# IO4-IR-Detector-GBunza-Fingers.net
KiCad netlist of a schematic drawn in EAGLE
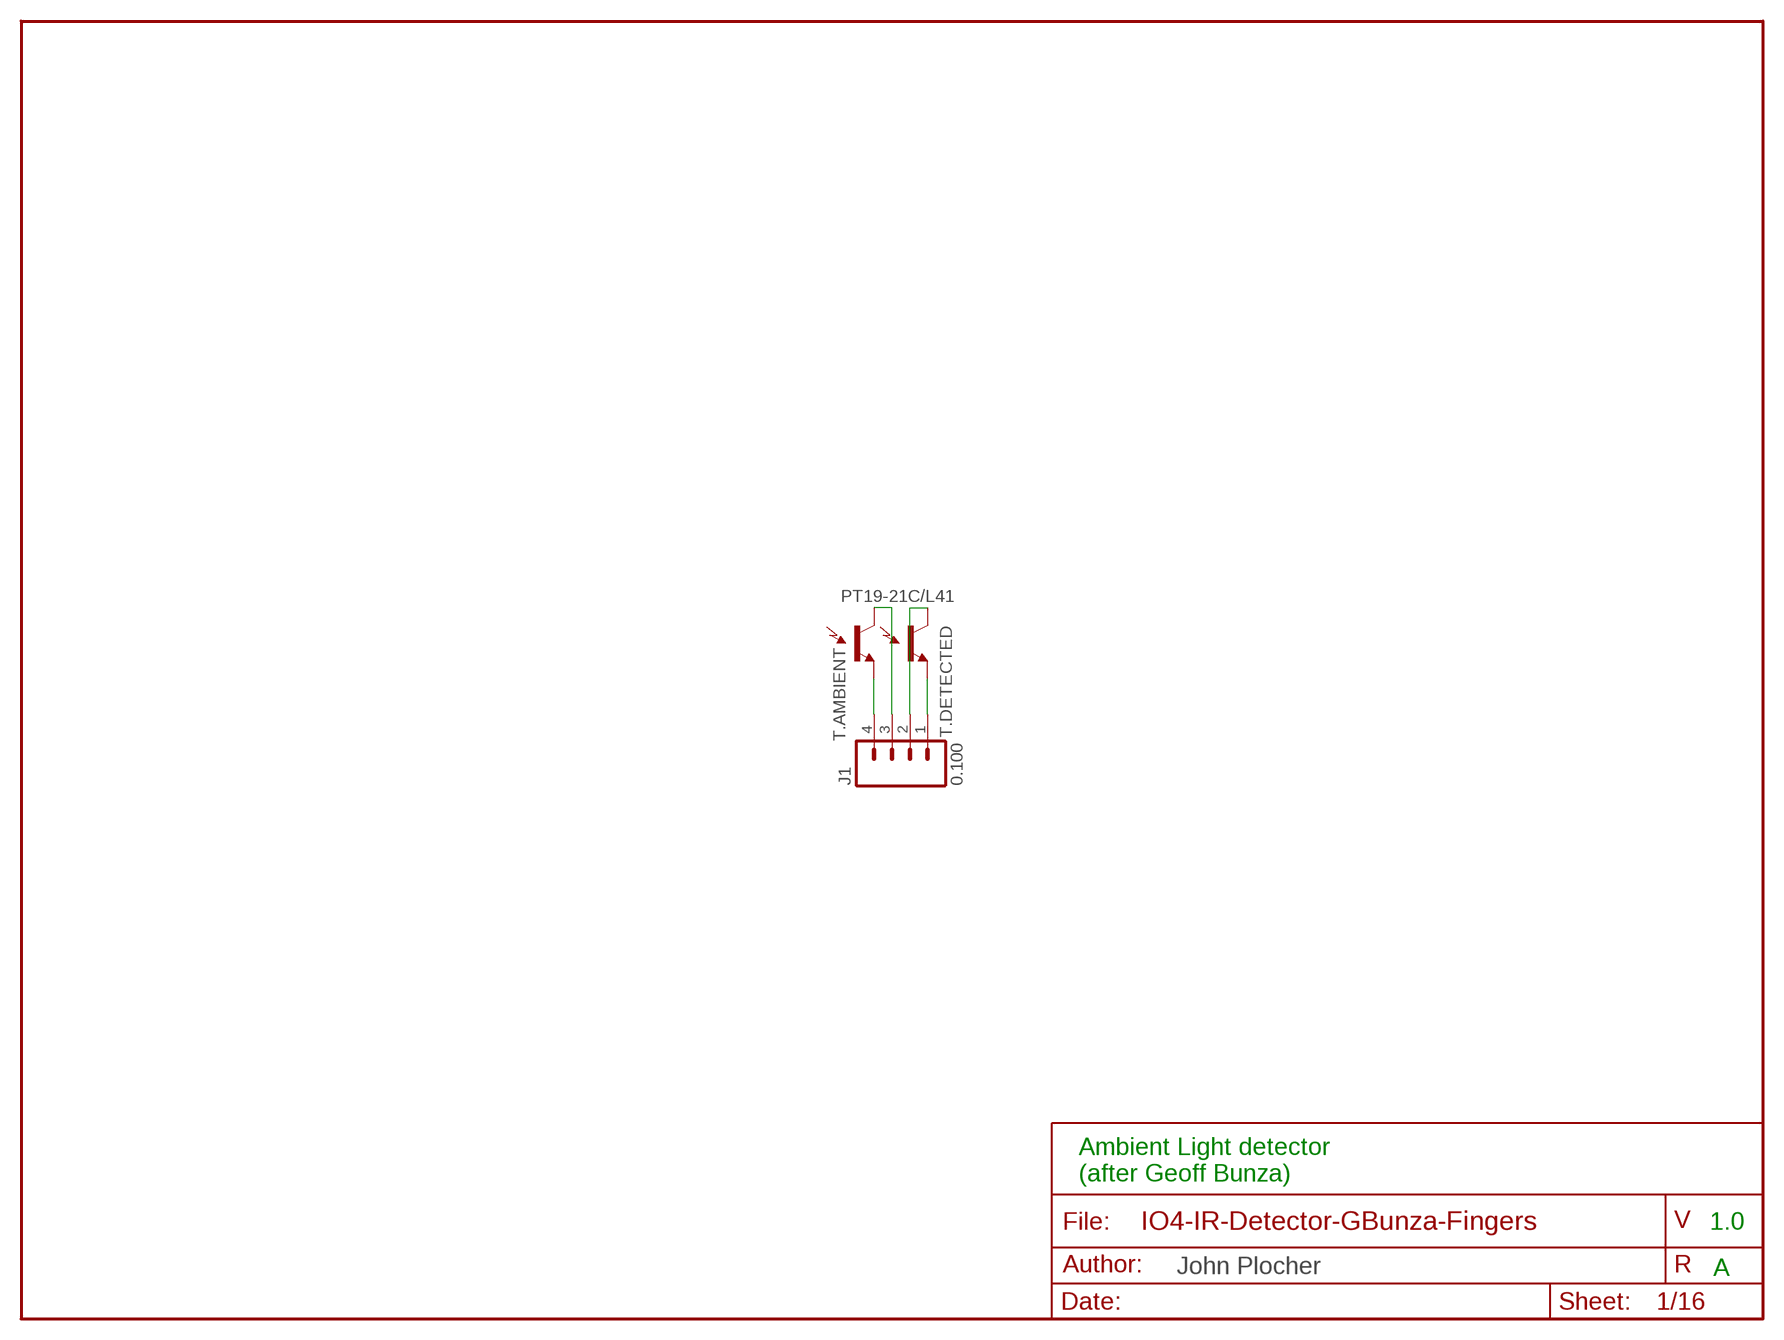
[diagram p0: schematic, sheet 1]
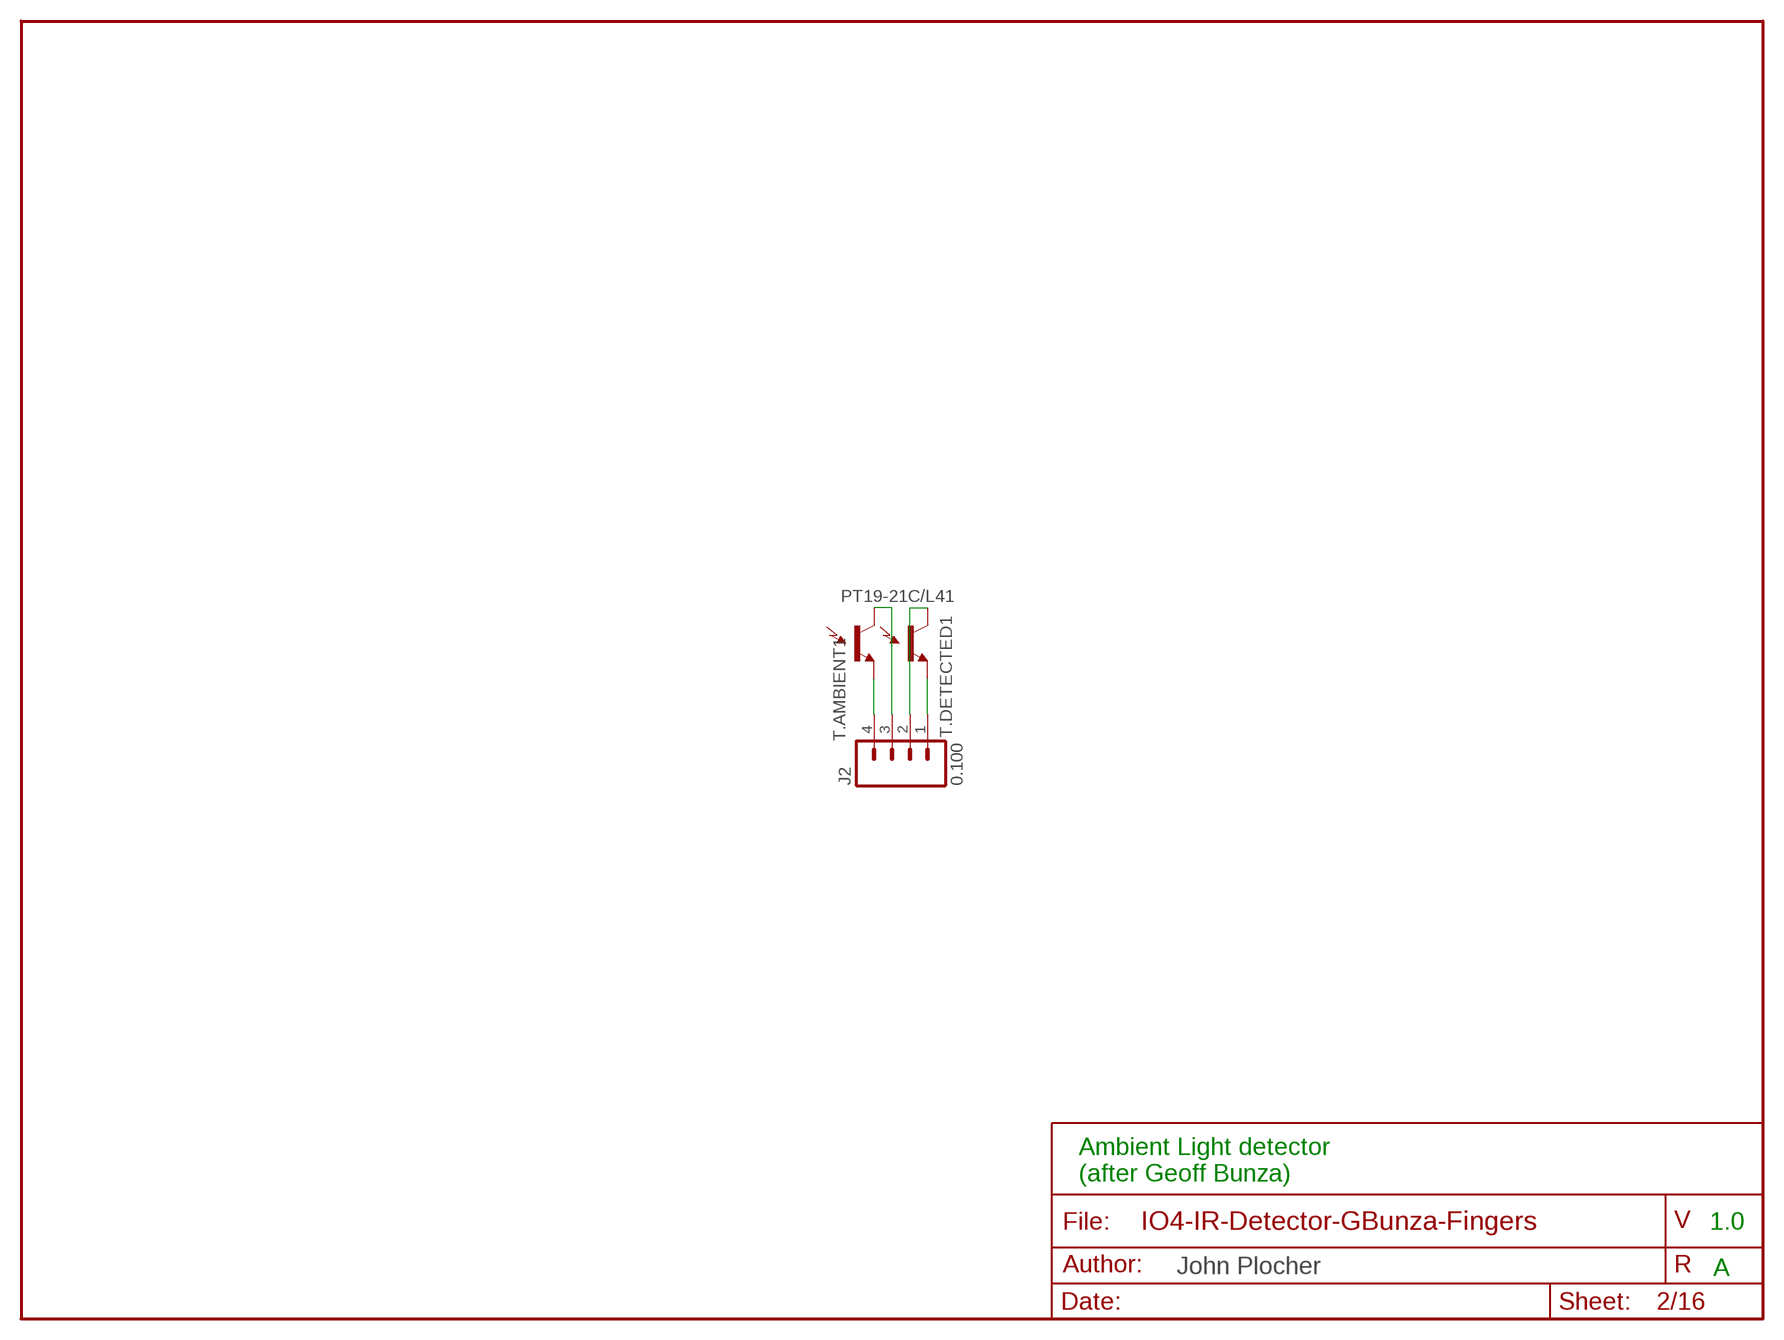
[diagram p1: schematic, sheet 2]
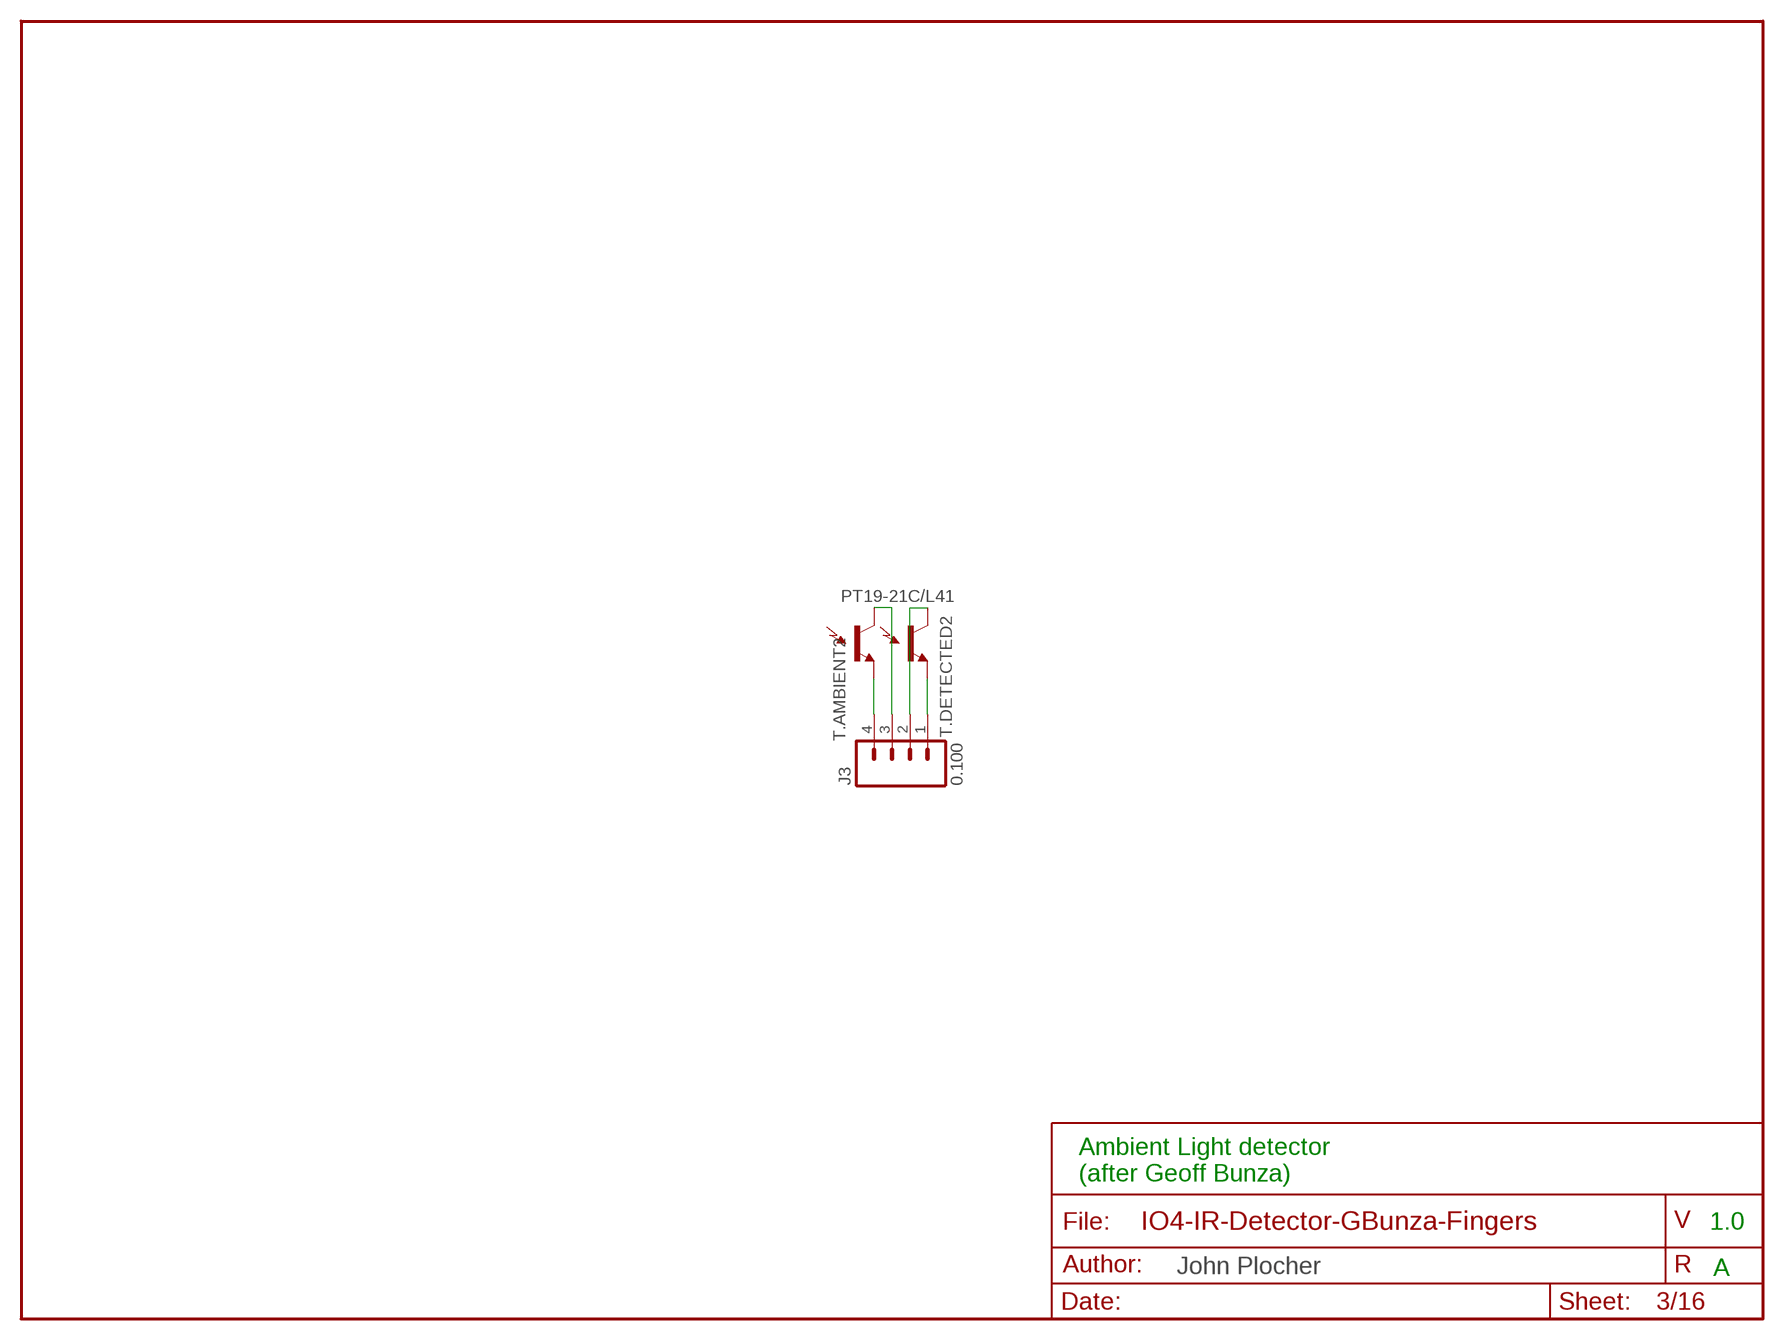
[diagram p2: schematic, sheet 3]
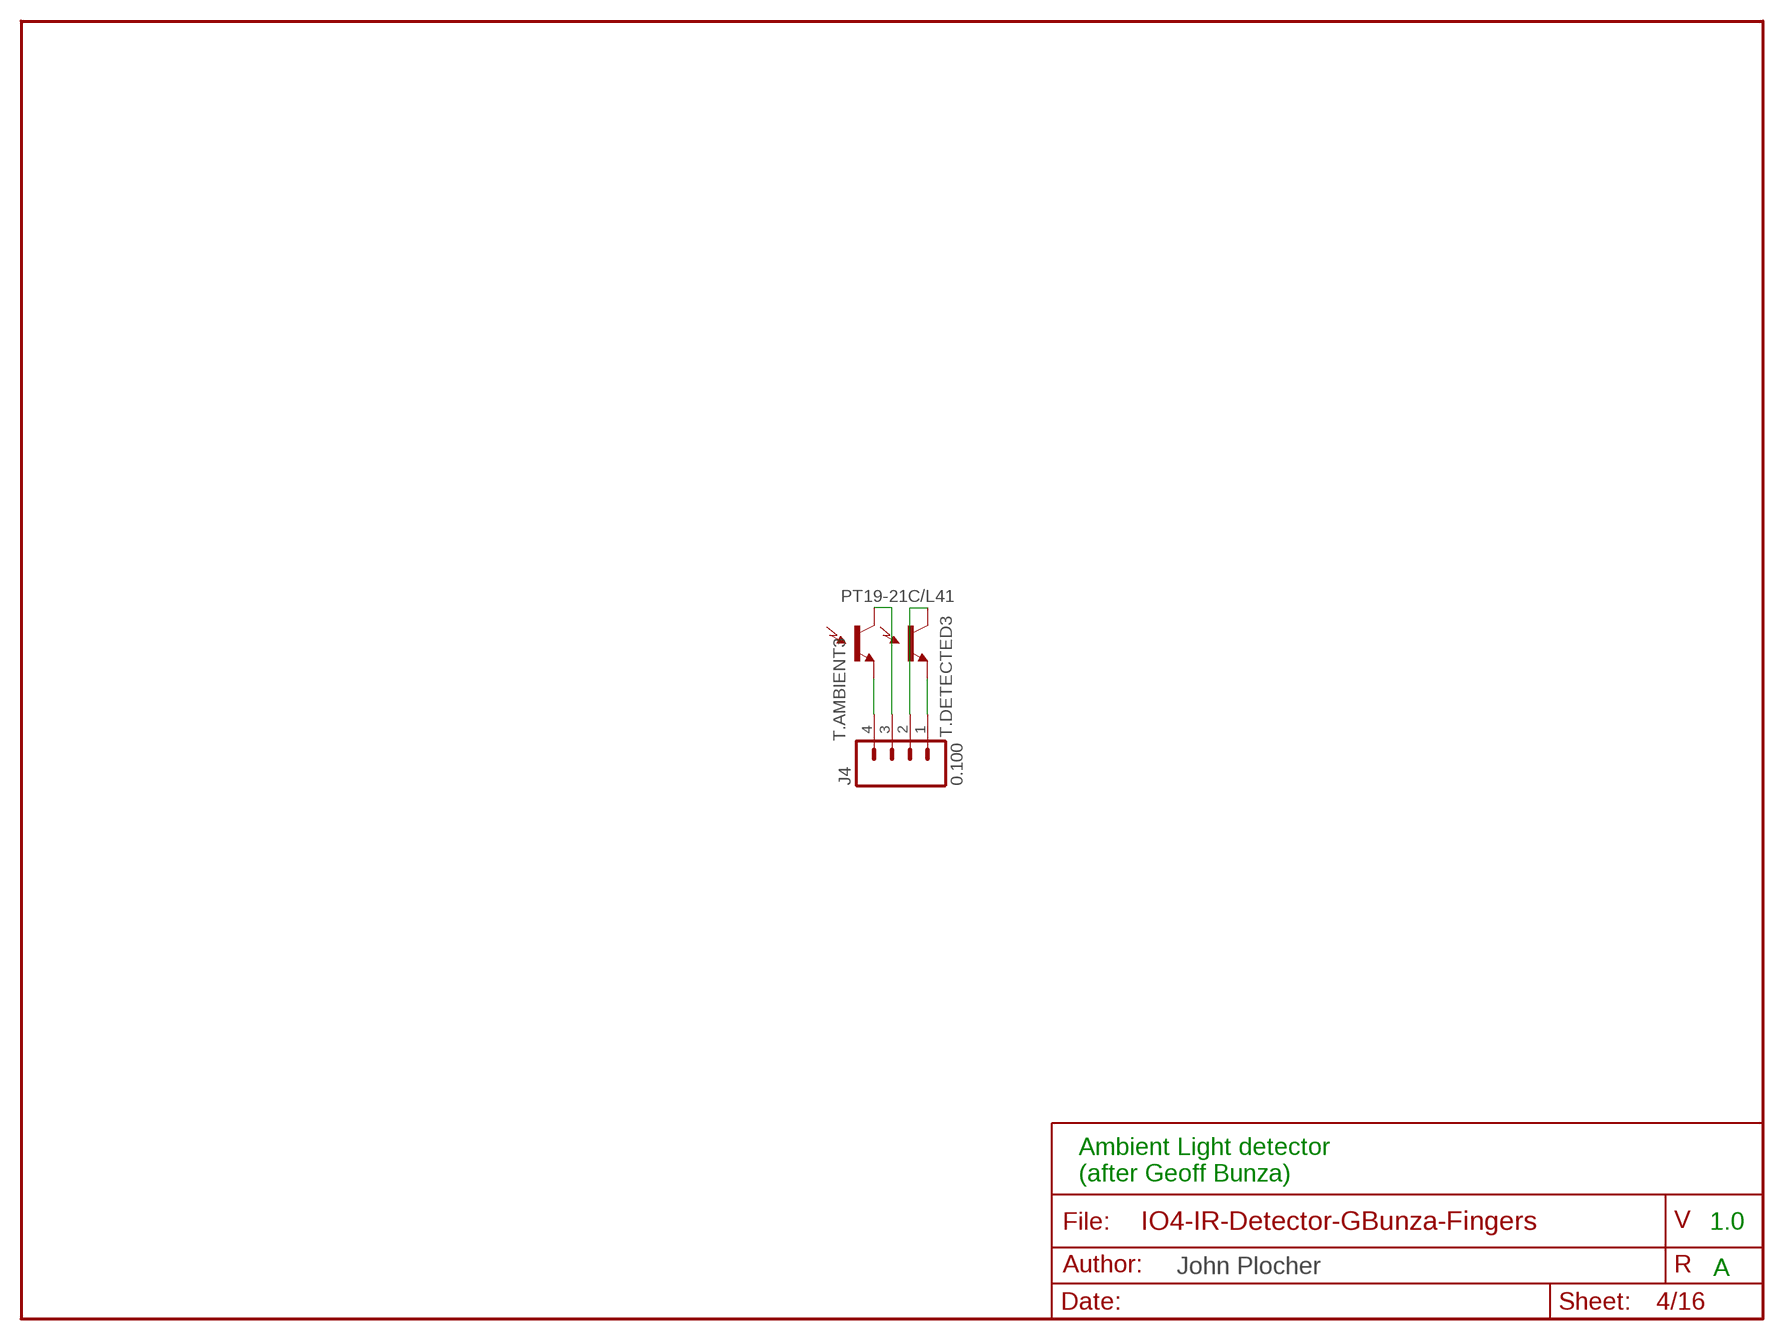
[diagram p3: schematic, sheet 4]
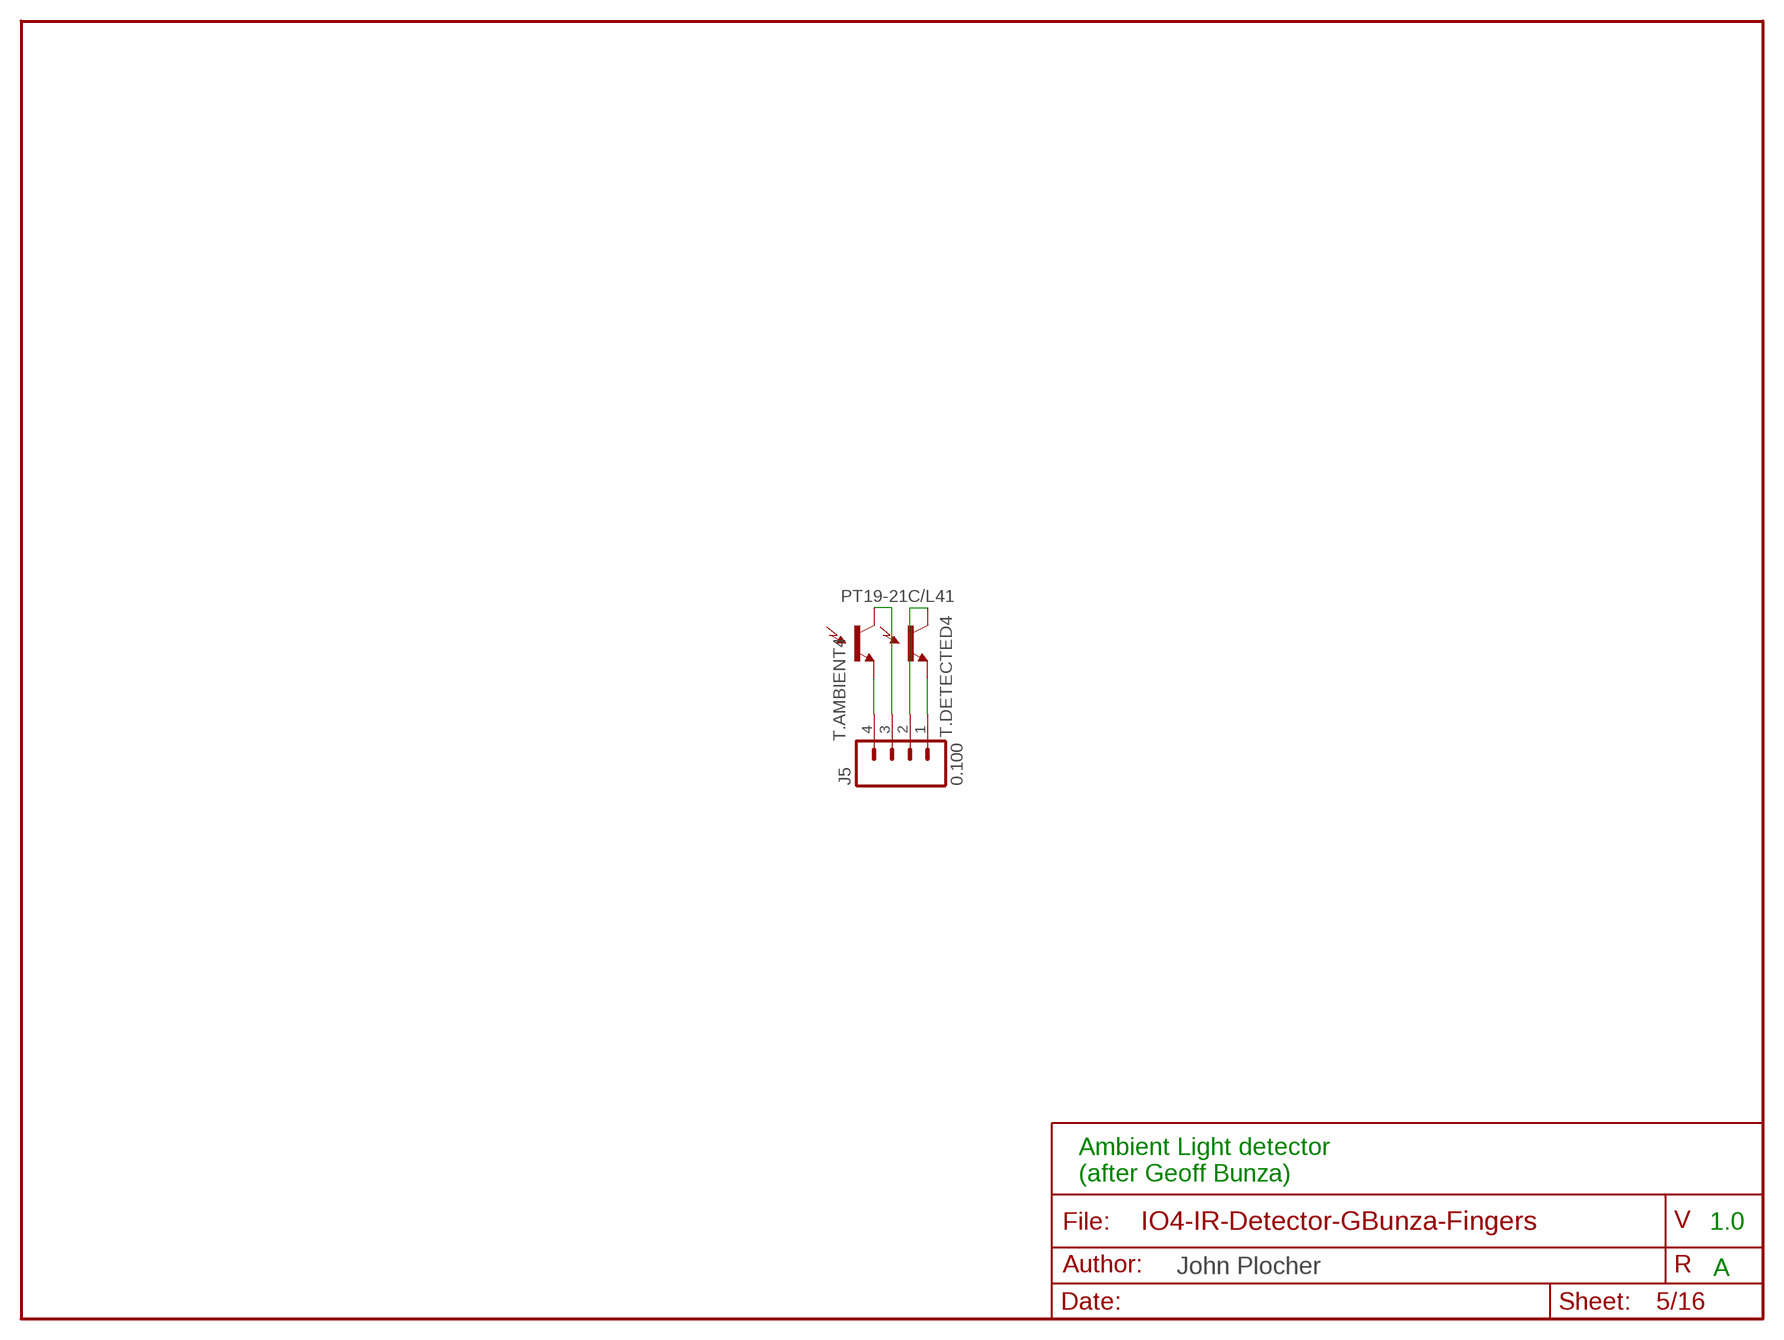
[diagram p4: schematic, sheet 5]
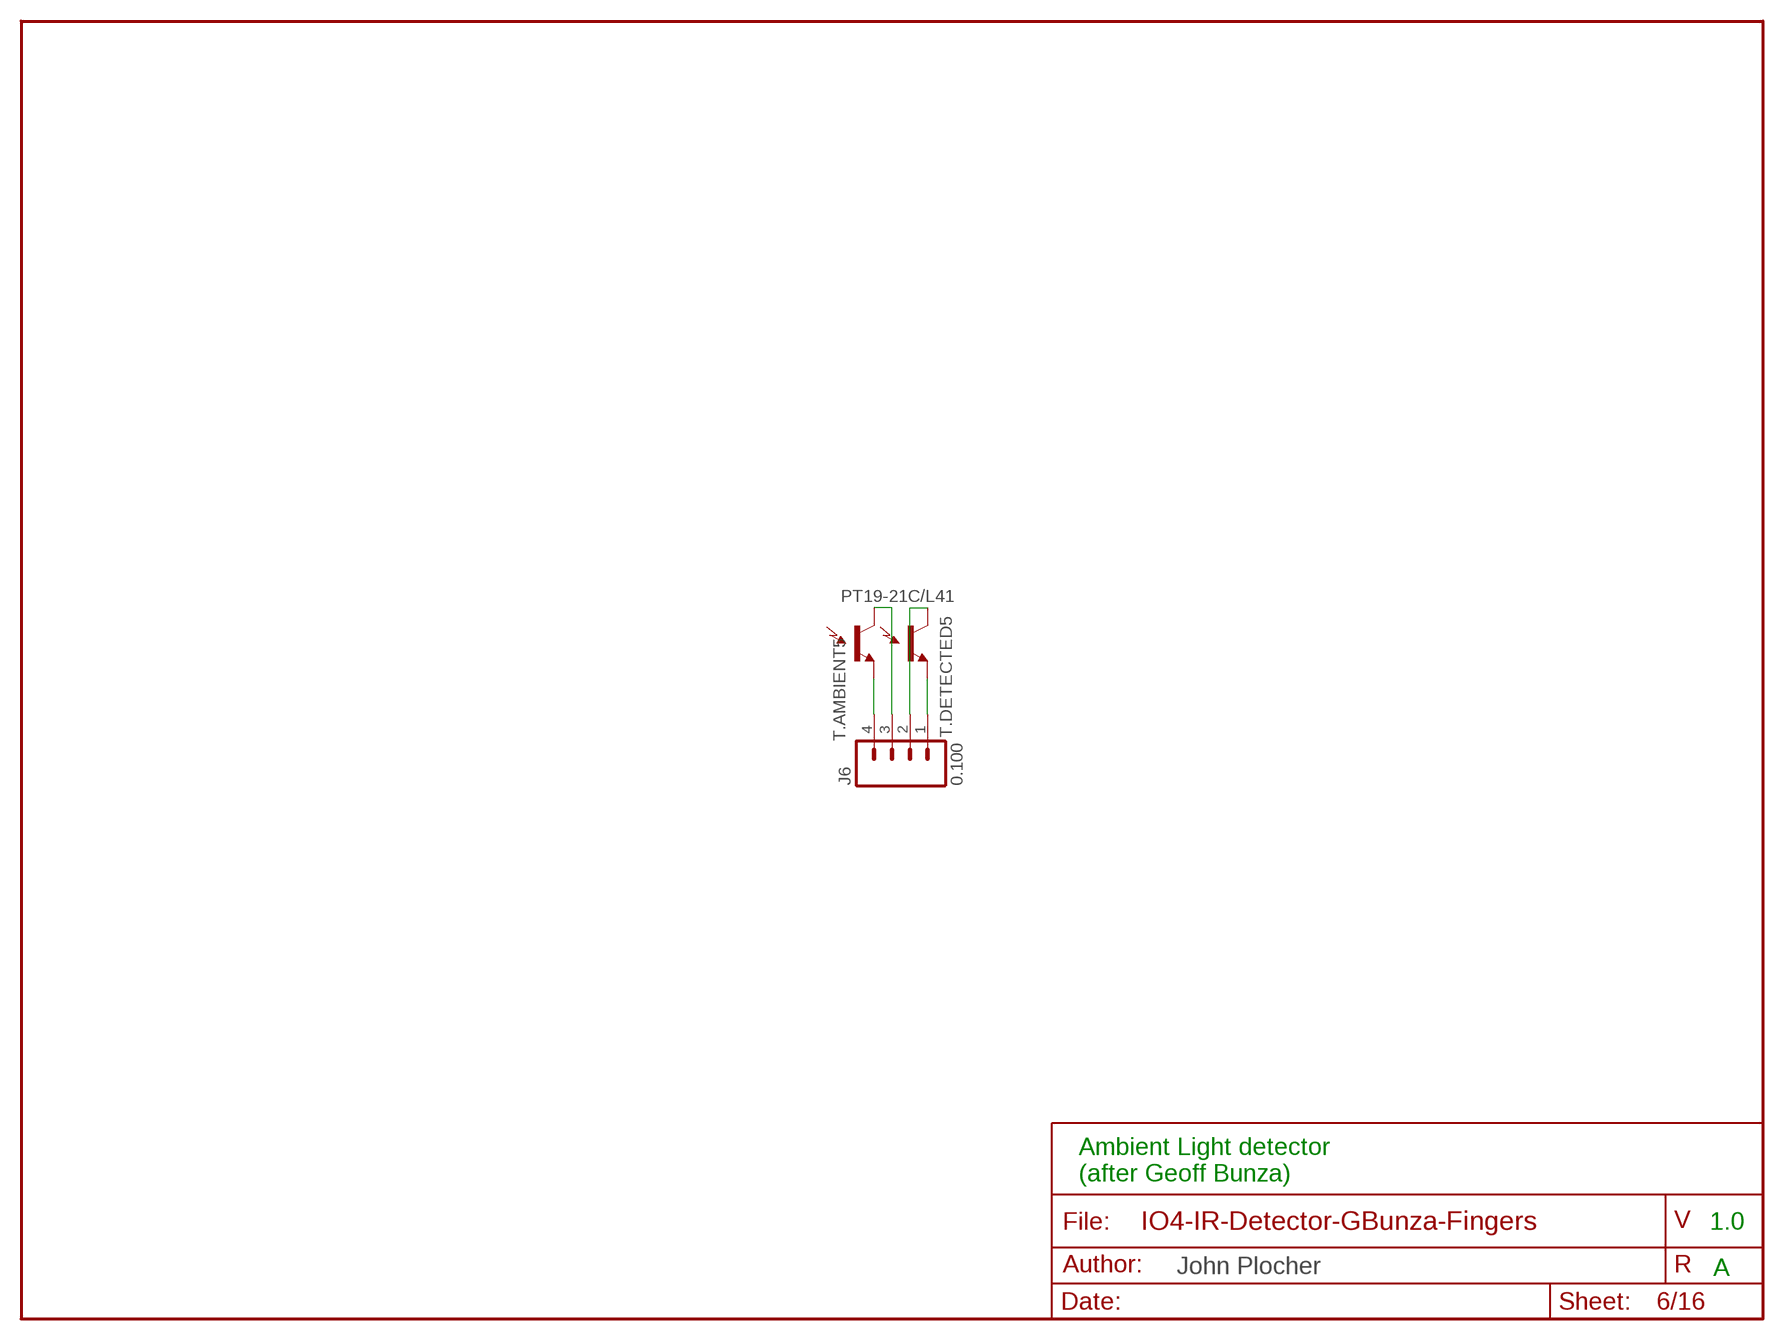
[diagram p5: schematic, sheet 6]
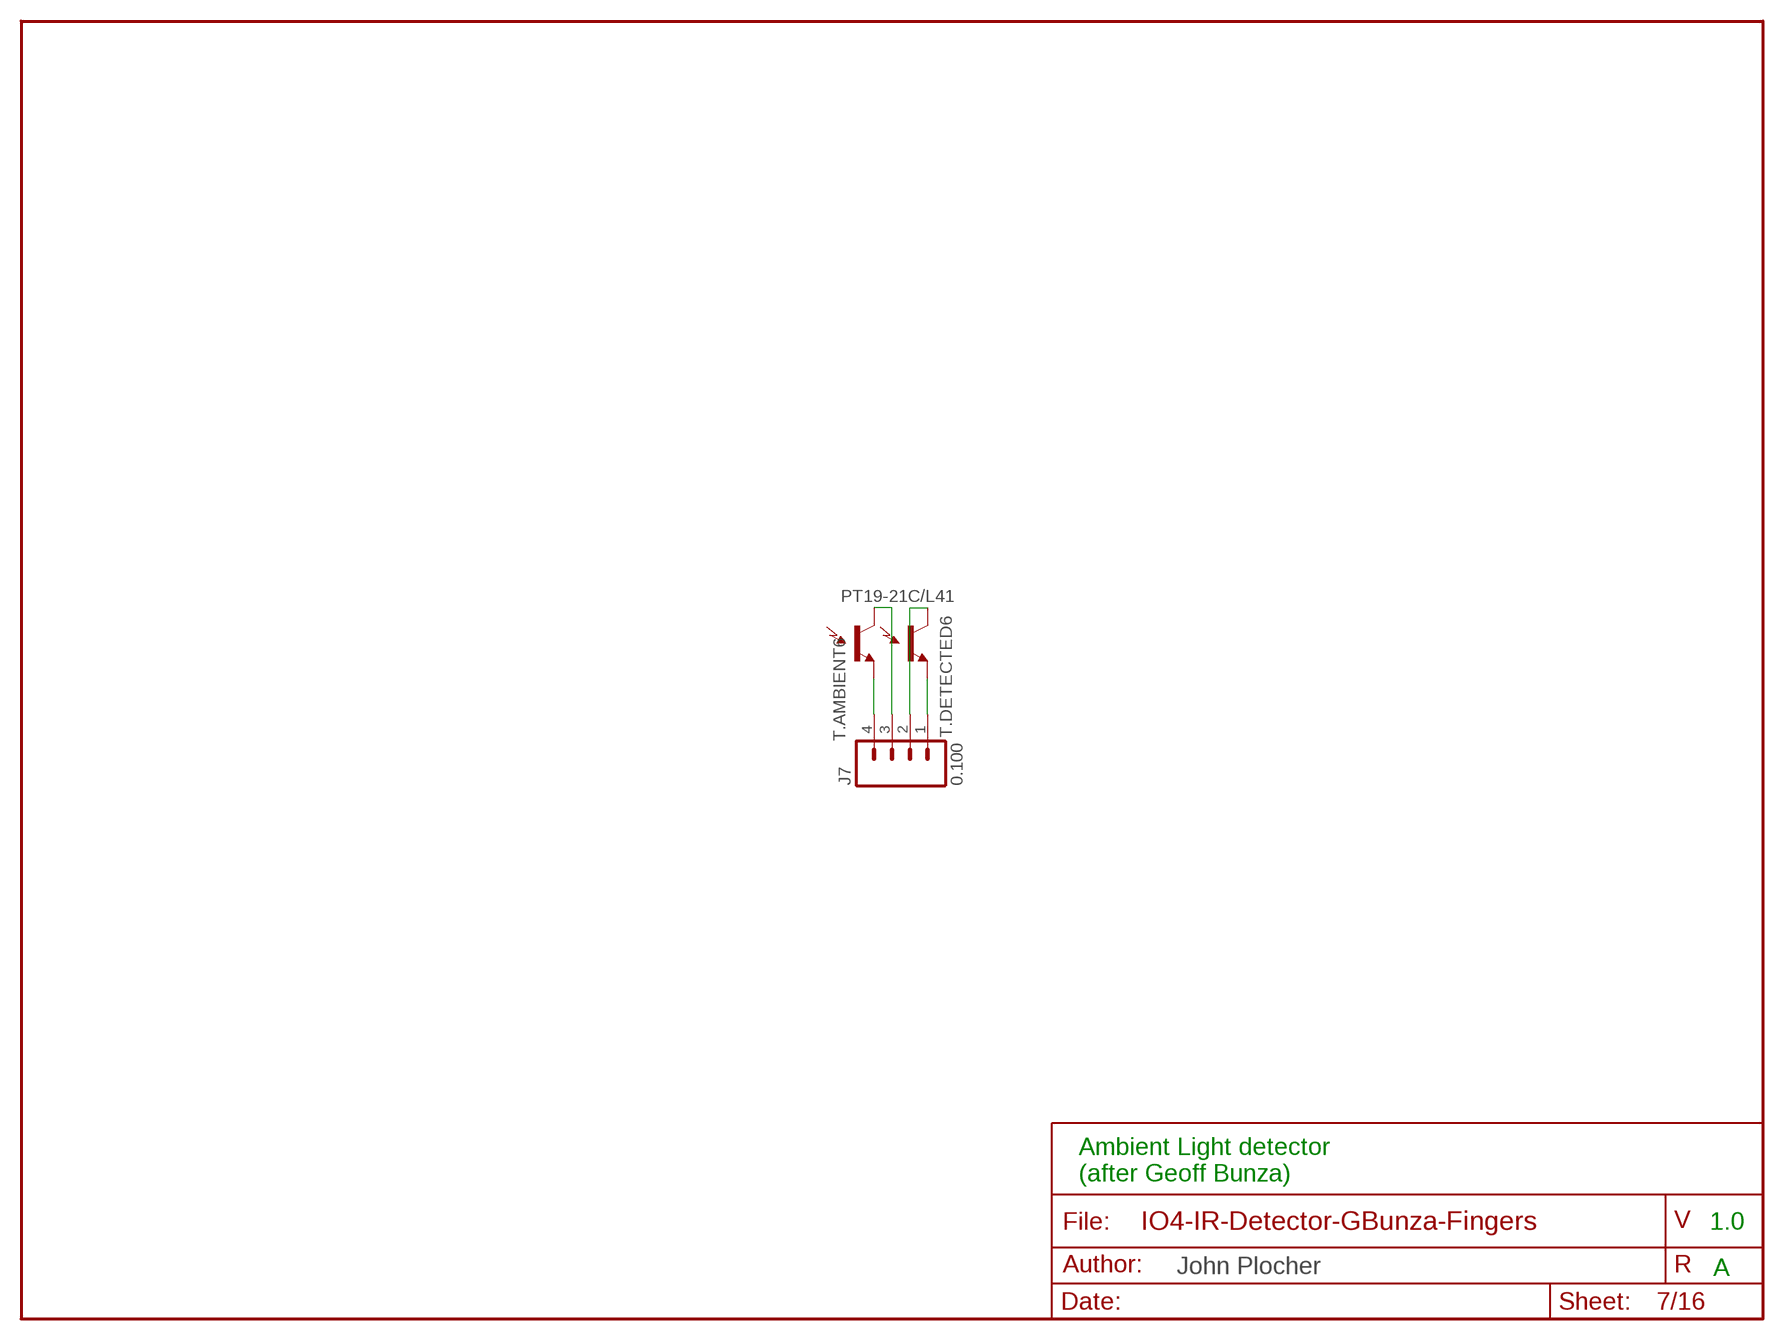
[diagram p6: schematic, sheet 7]
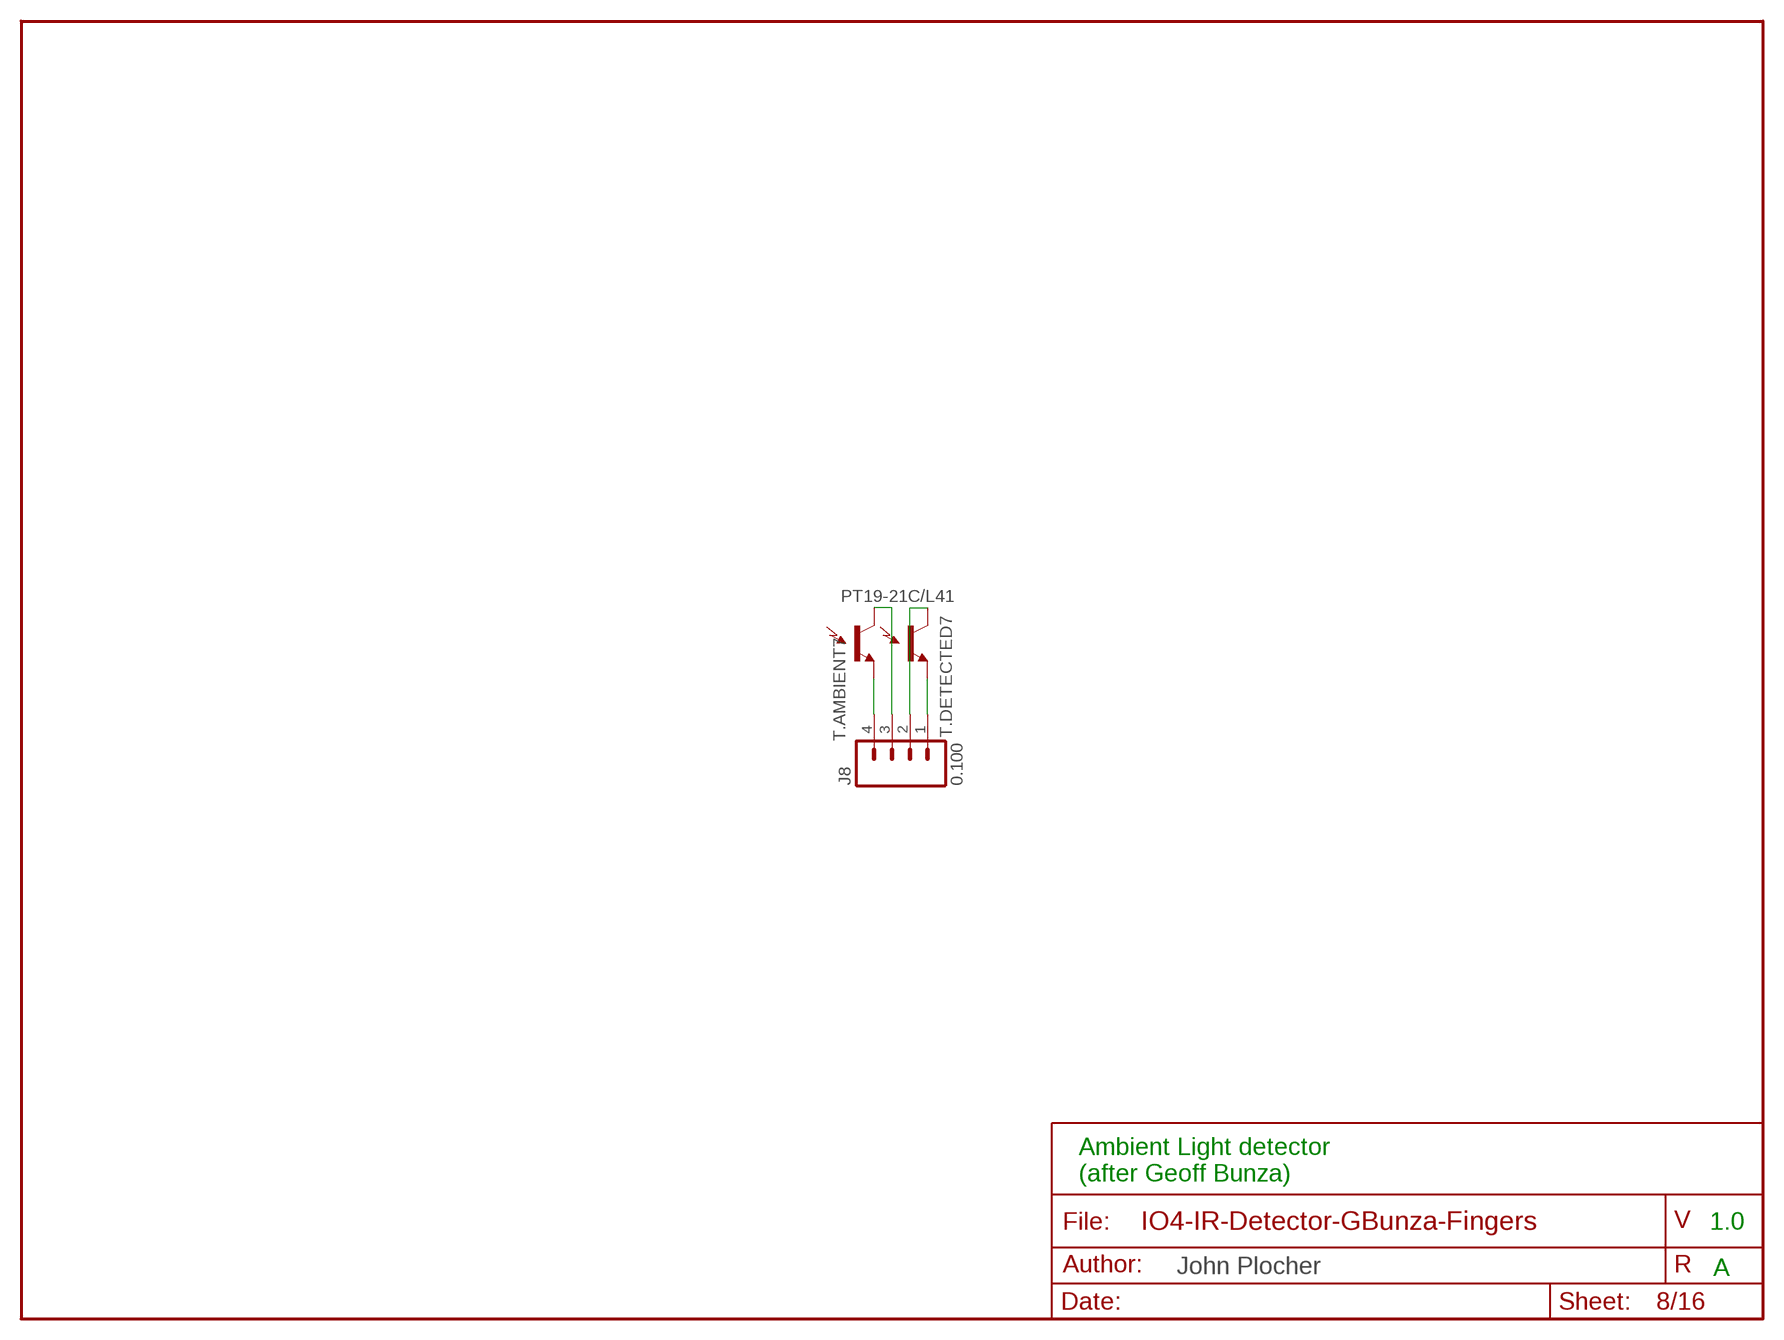
[diagram p7: schematic, sheet 8]
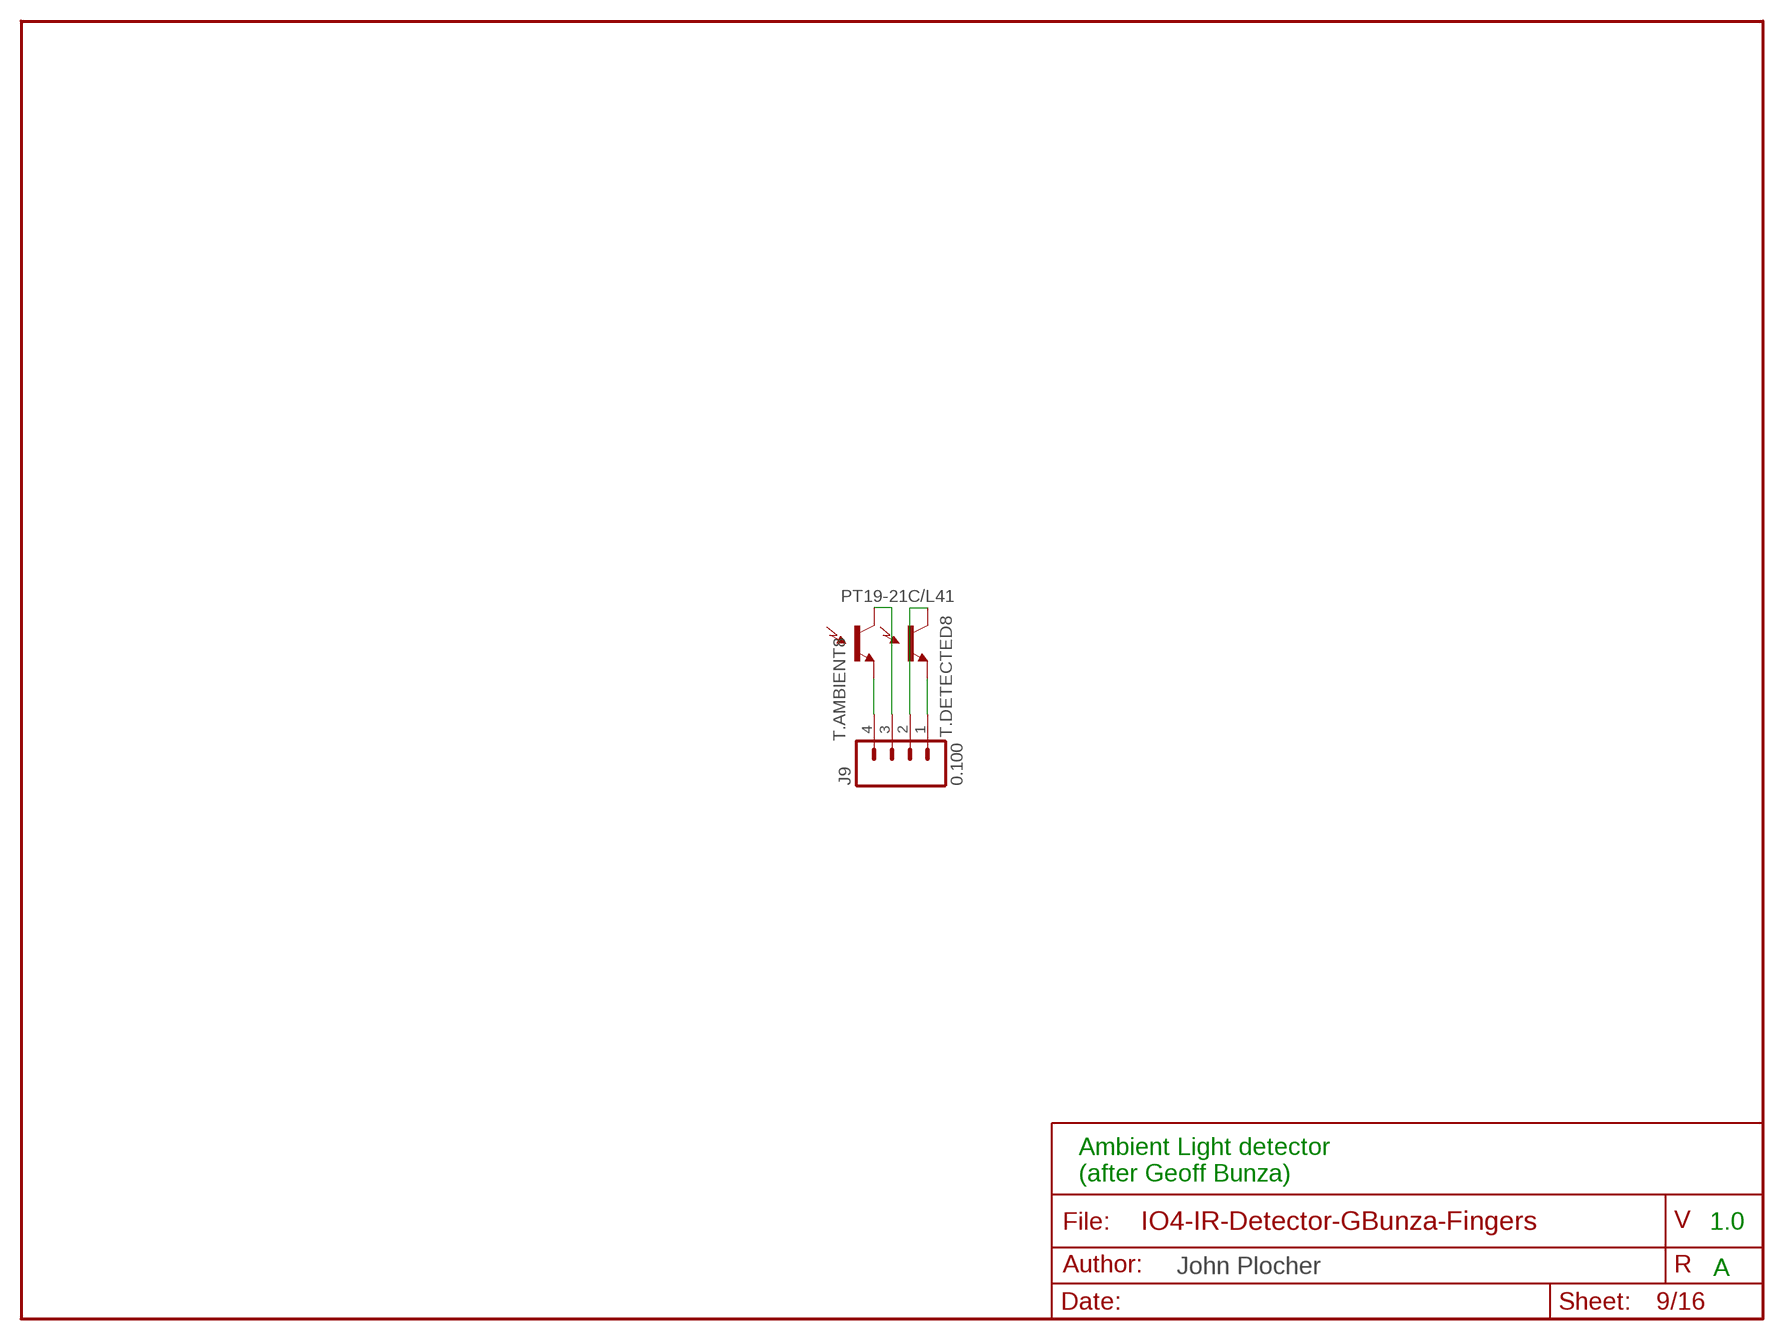
[diagram p8: schematic, sheet 9]
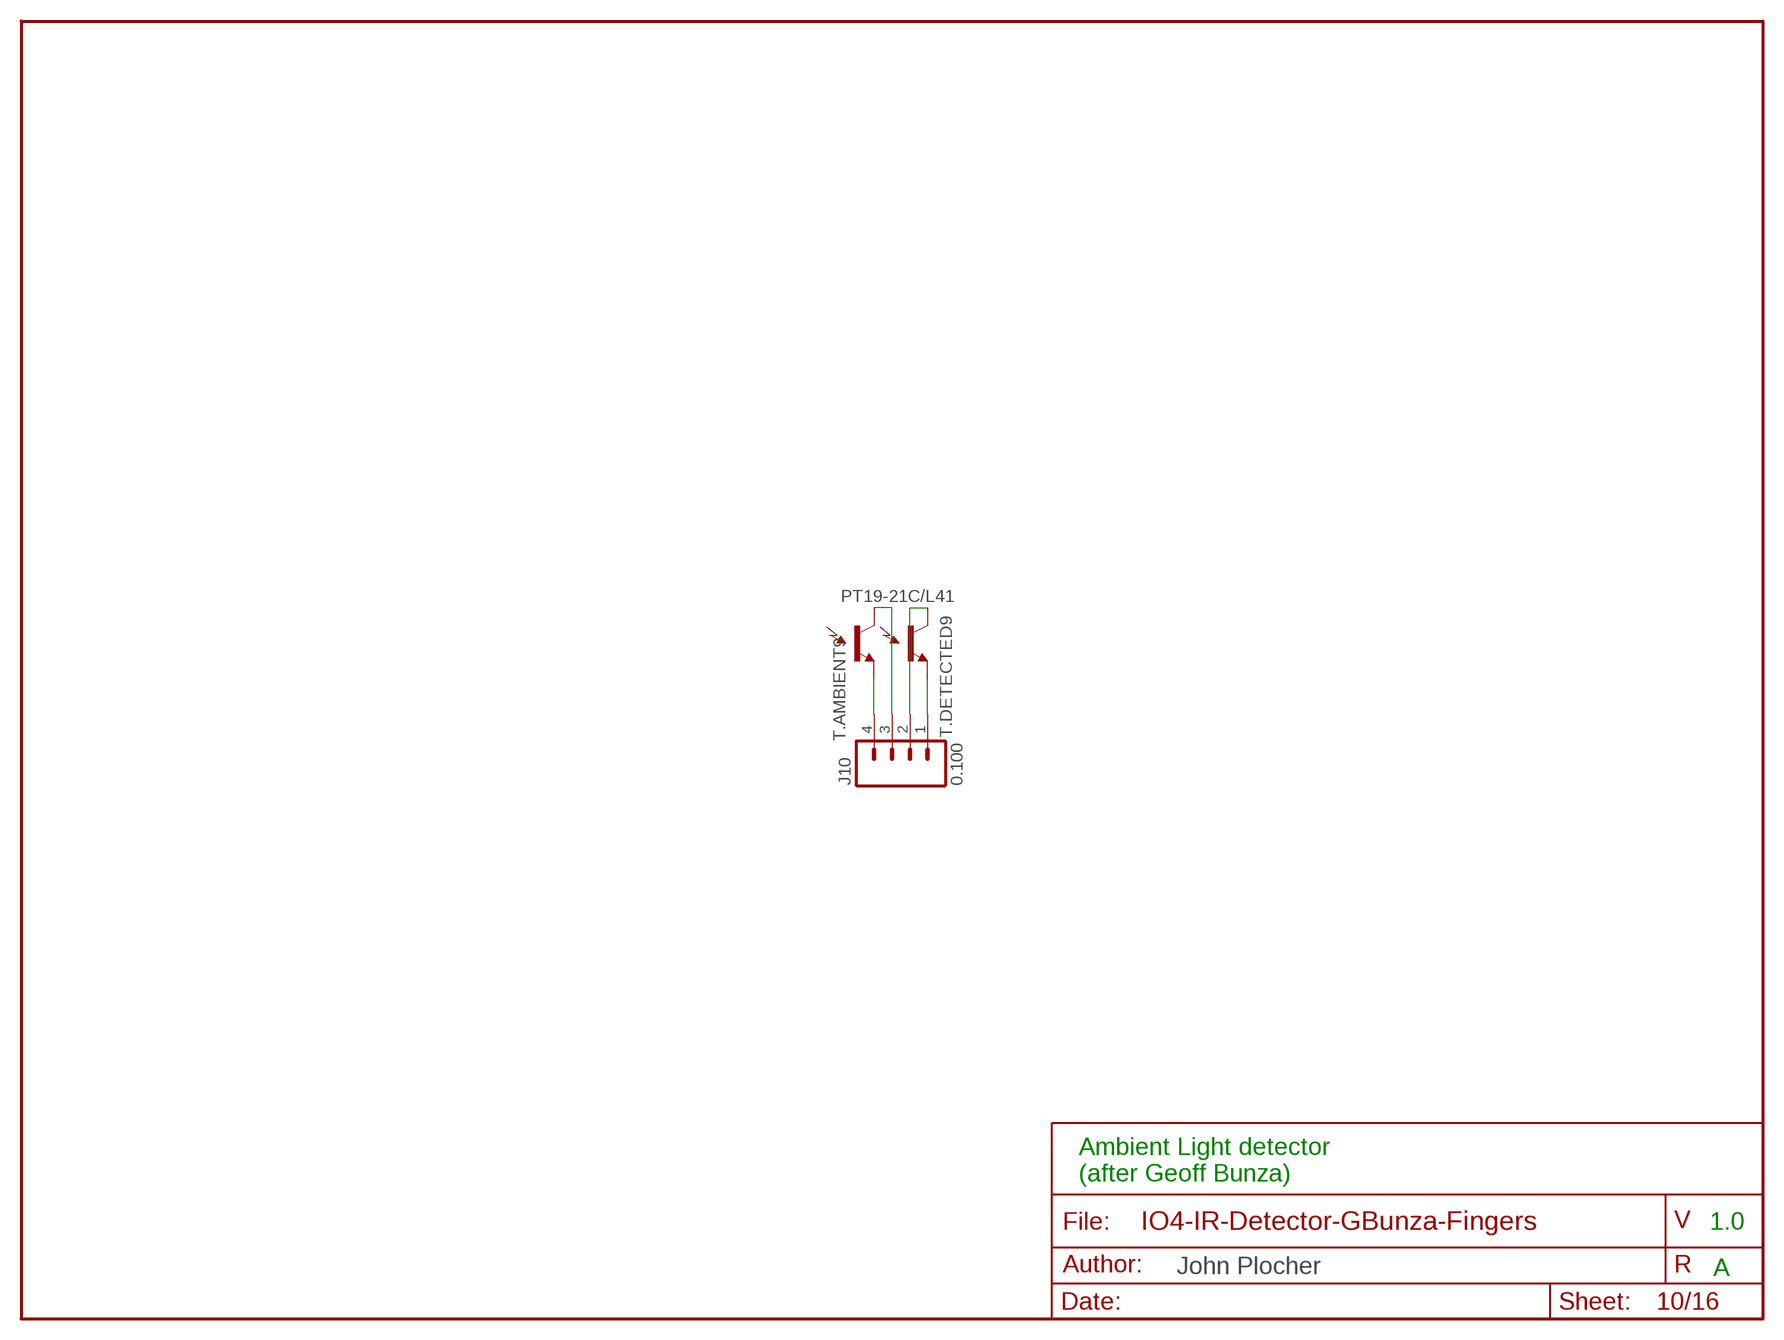
[diagram p9: schematic, sheet 10]
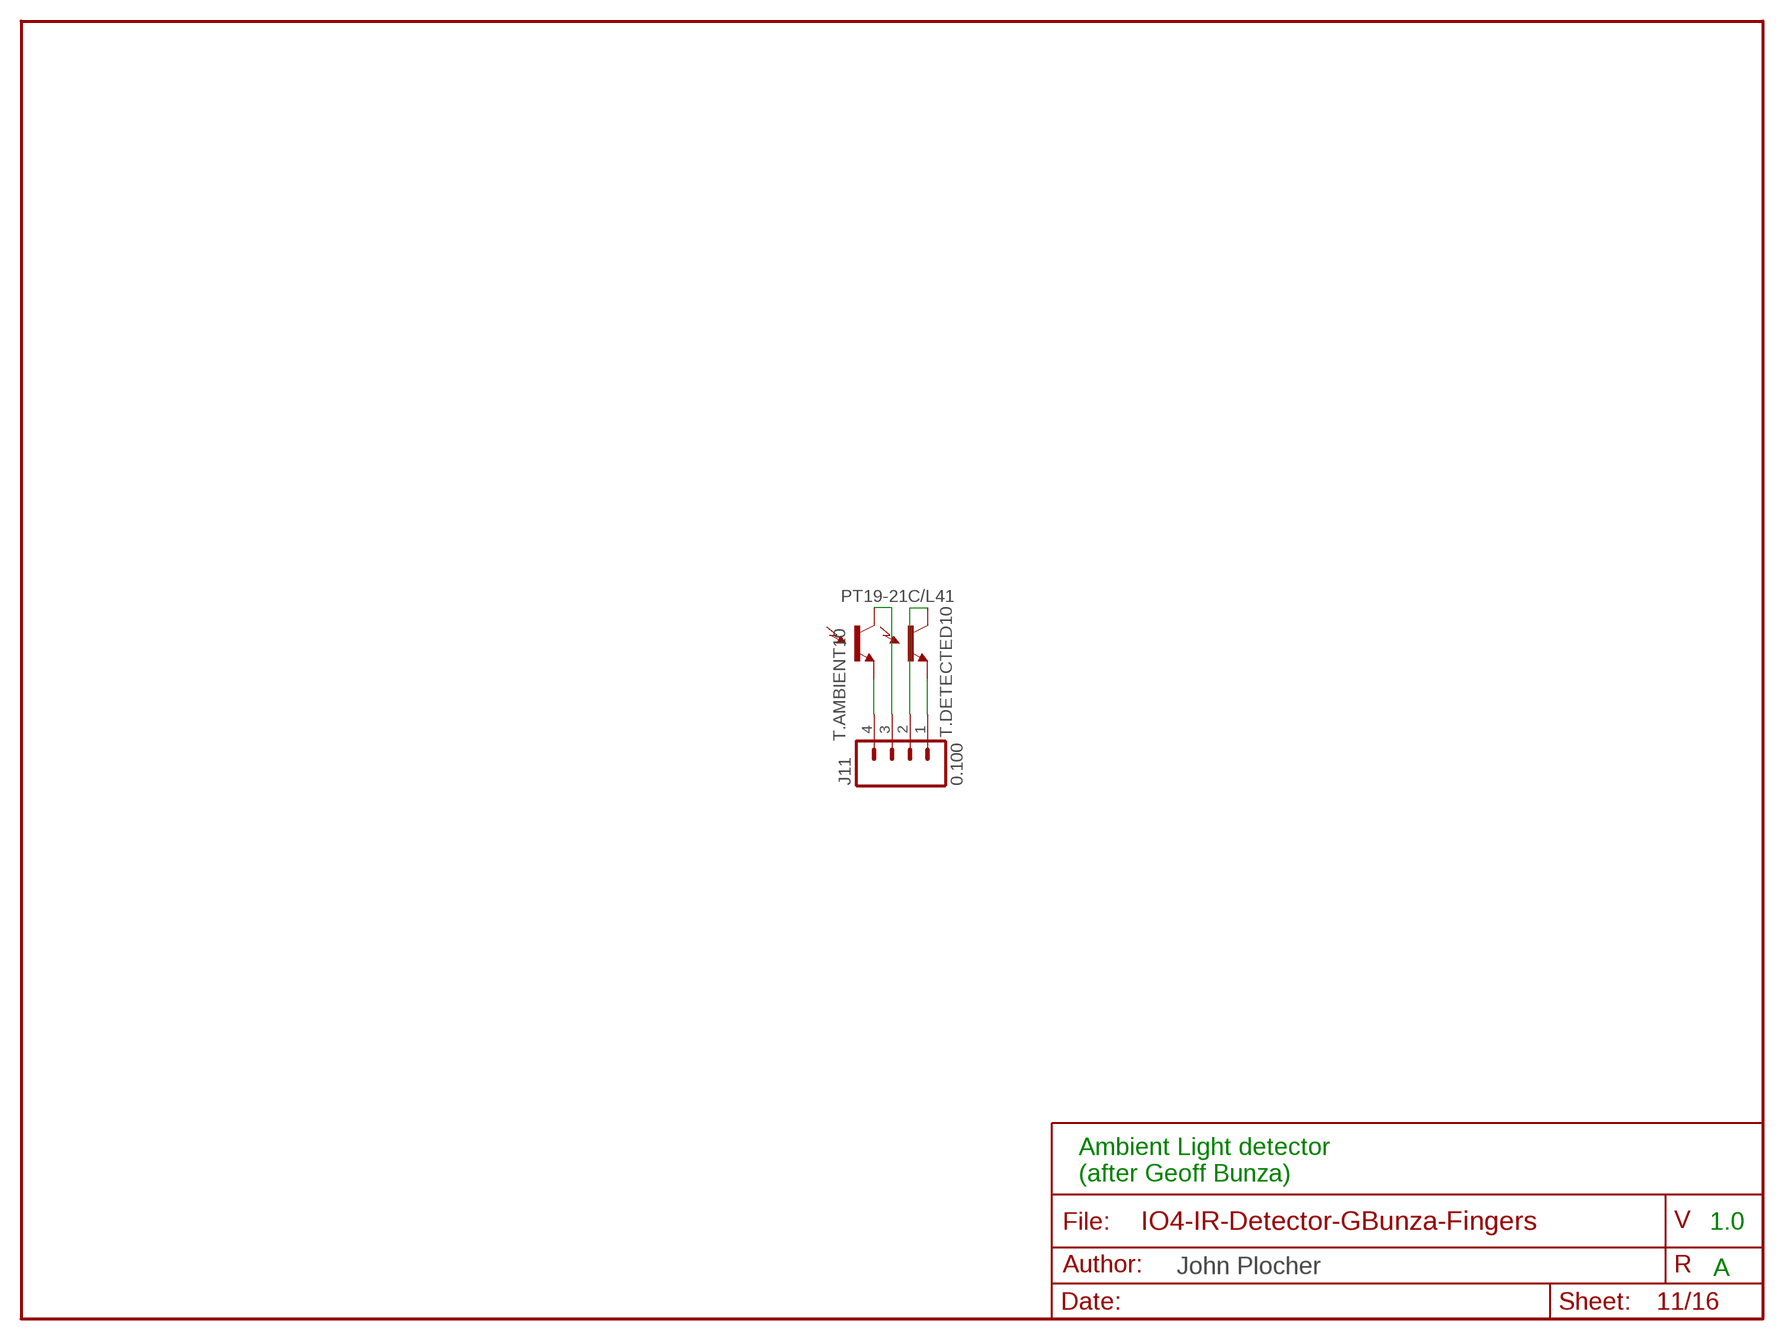
[diagram p10: schematic, sheet 11]
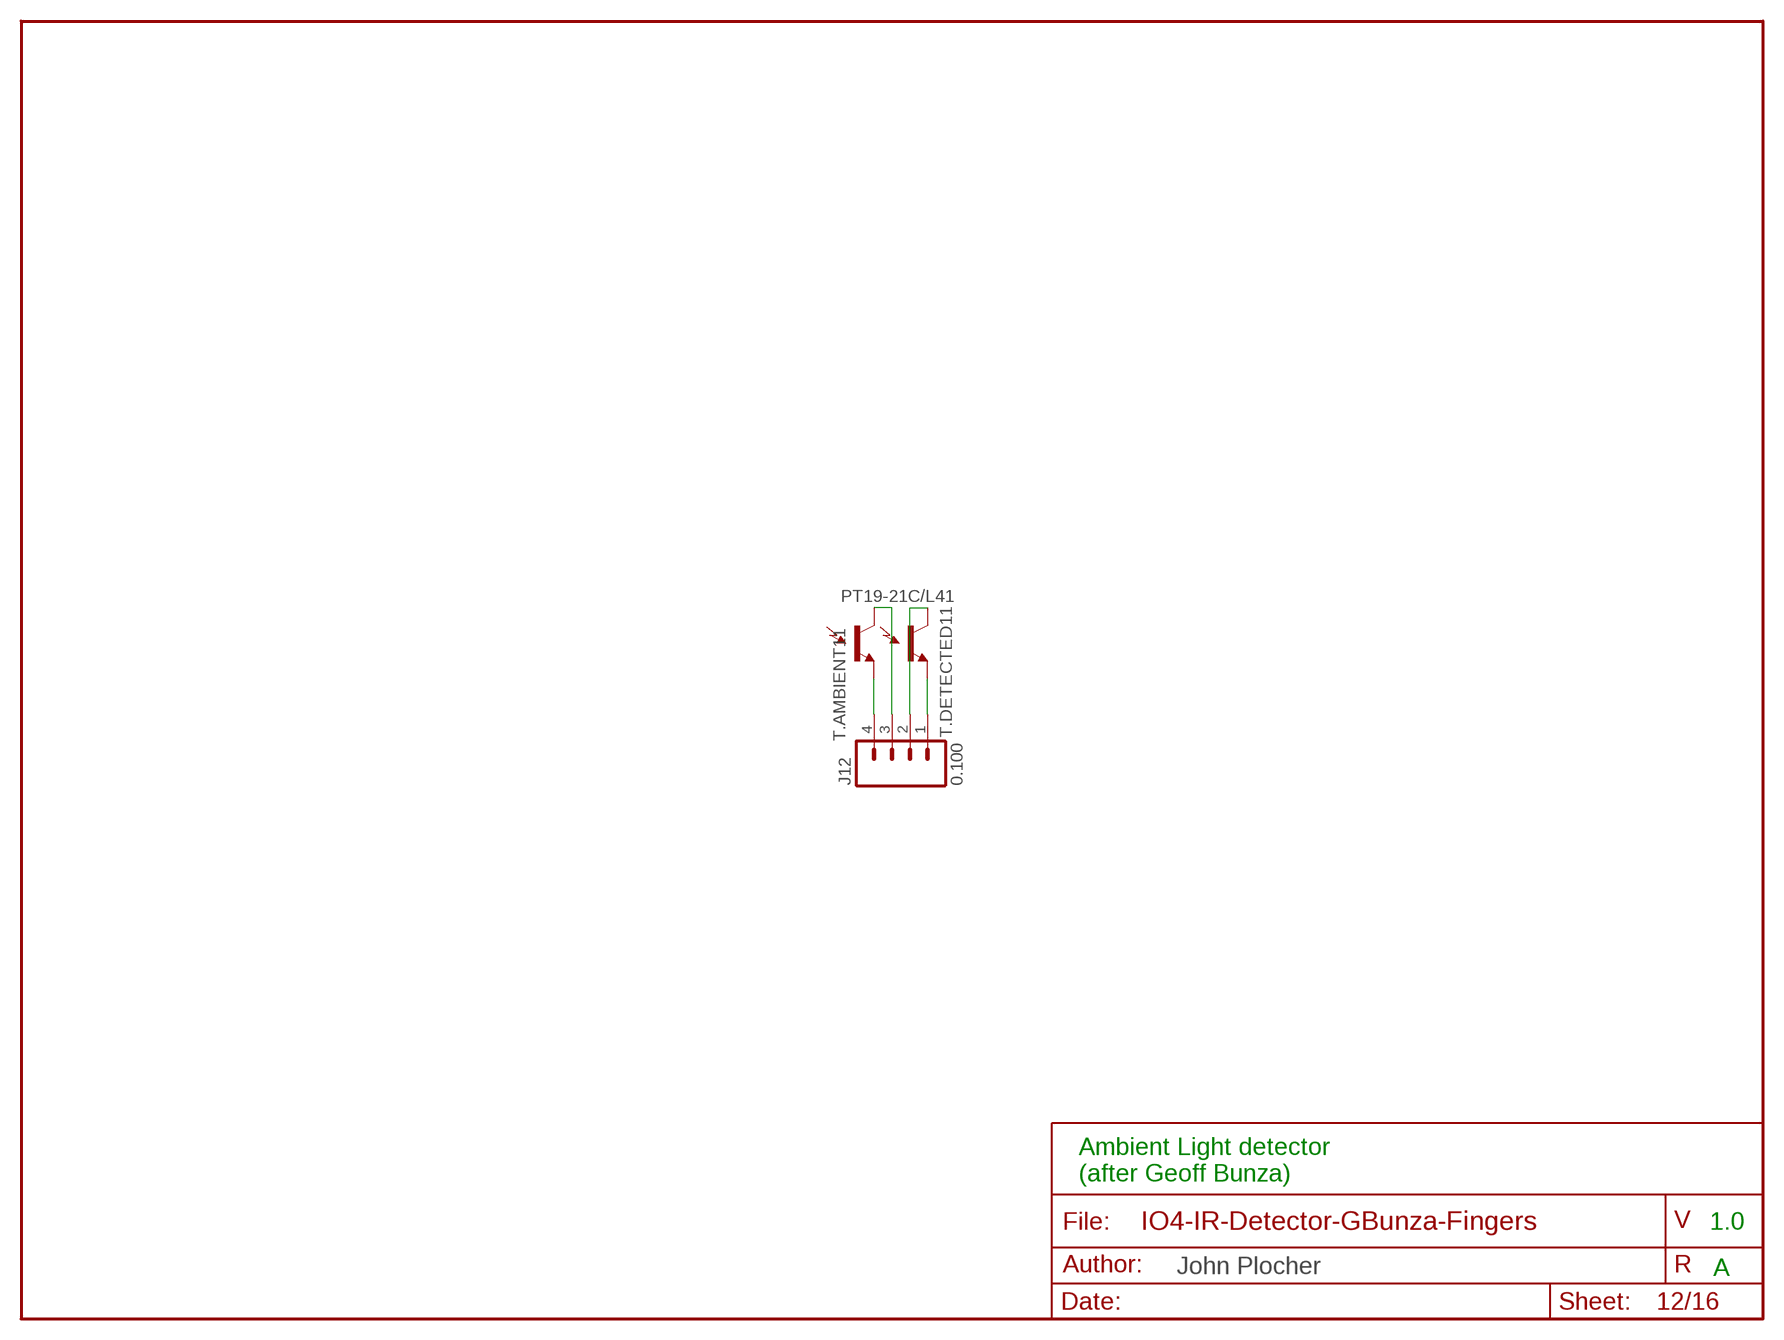
[diagram p11: schematic, sheet 12]
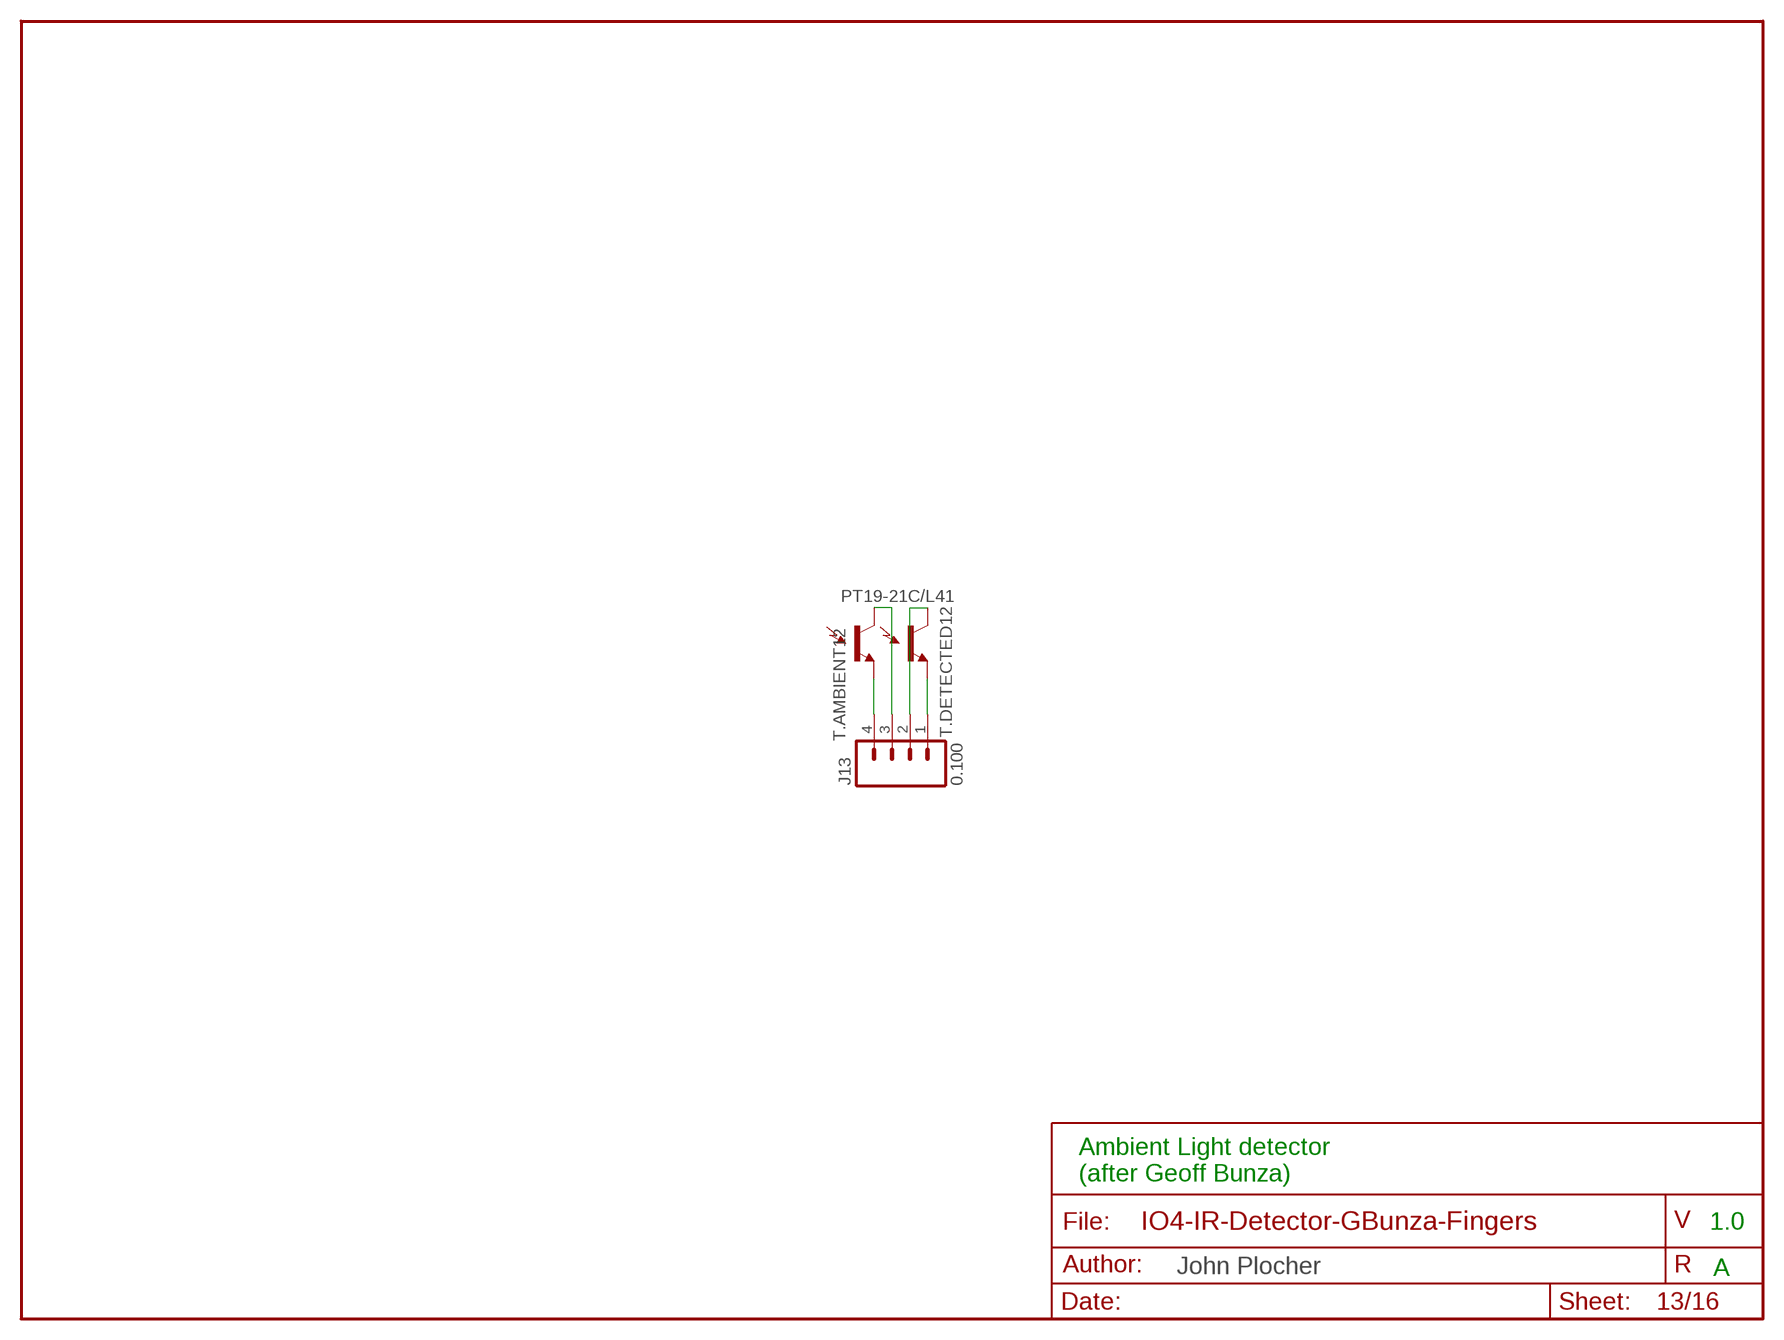
[diagram p12: schematic, sheet 13]
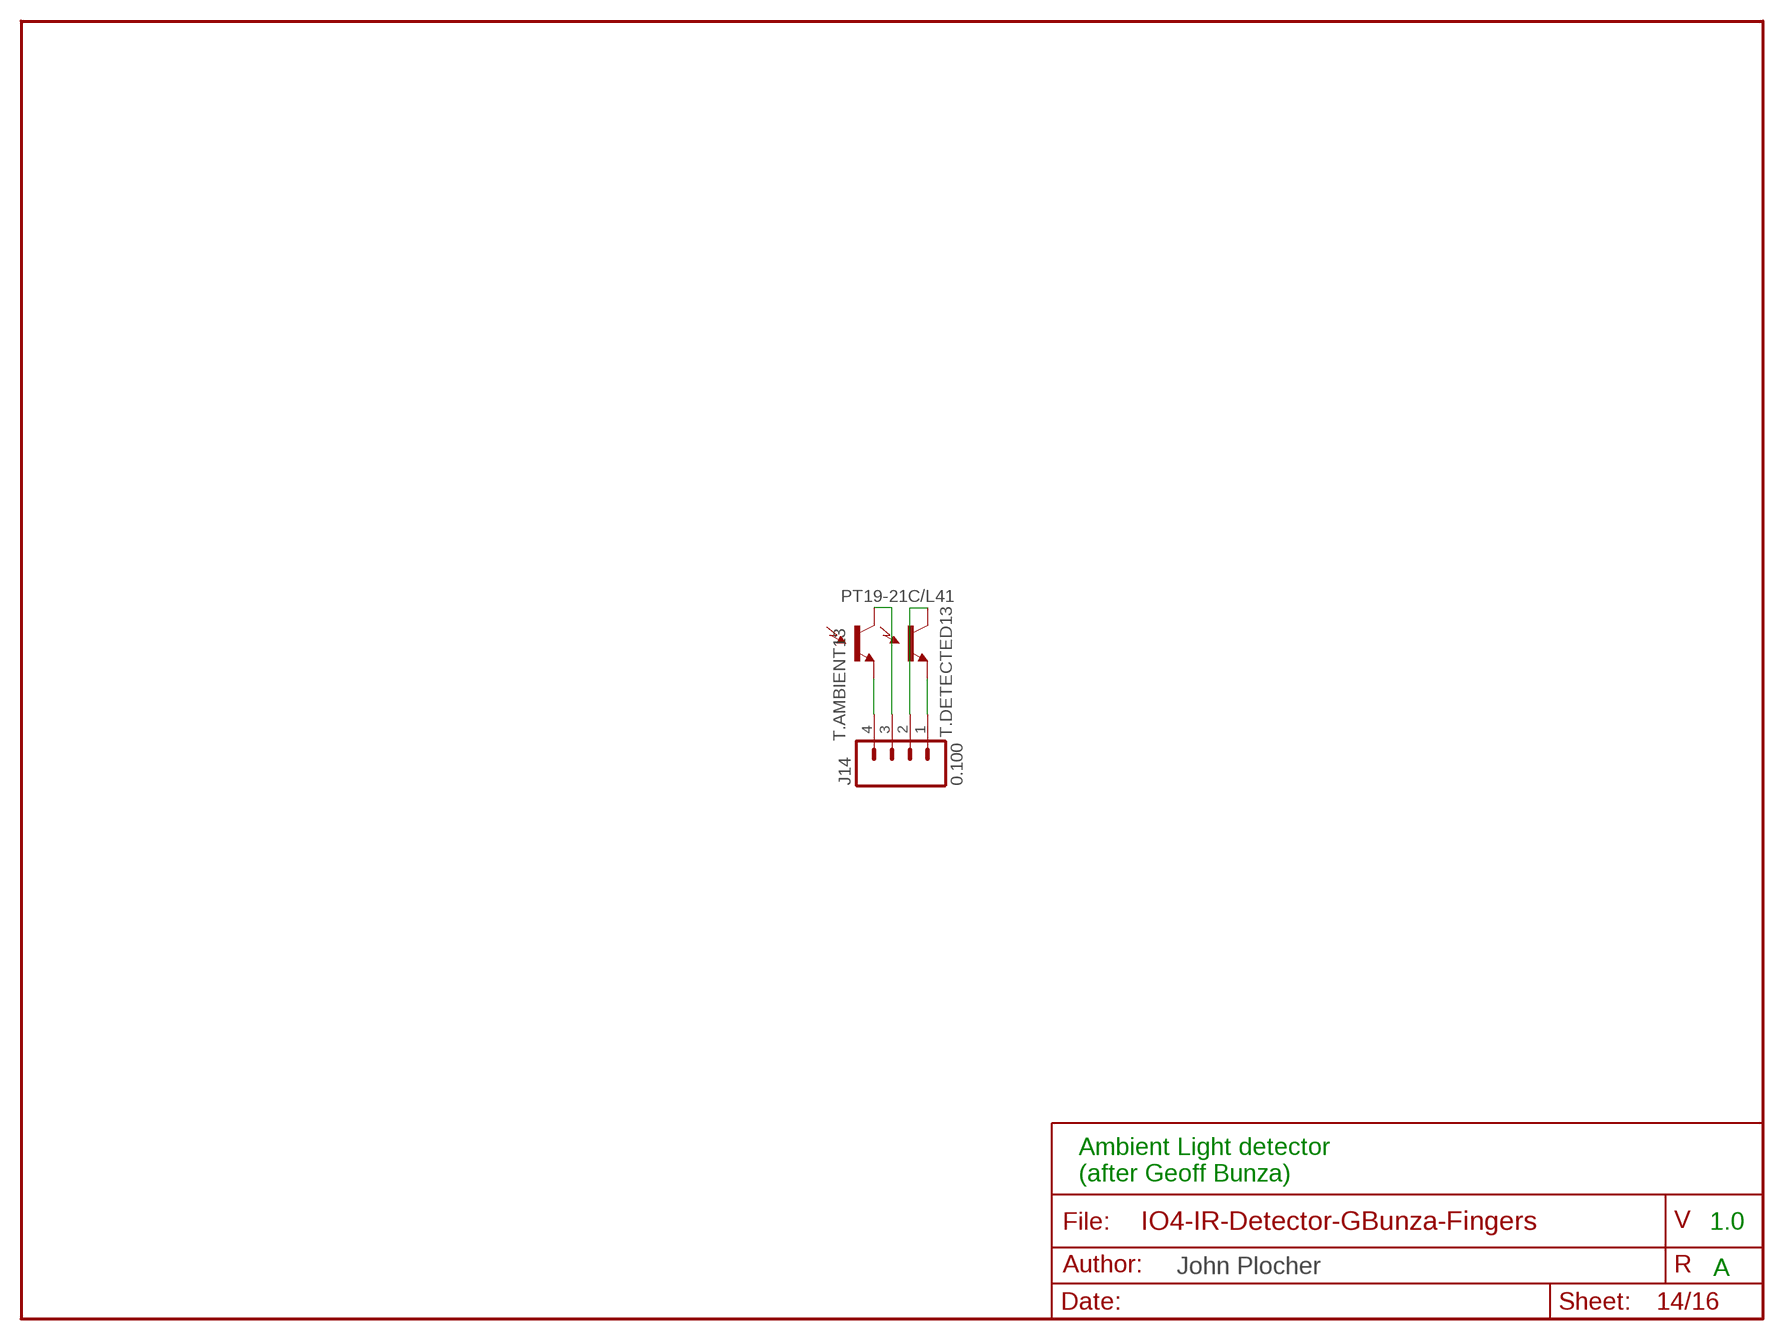
[diagram p13: schematic, sheet 14]
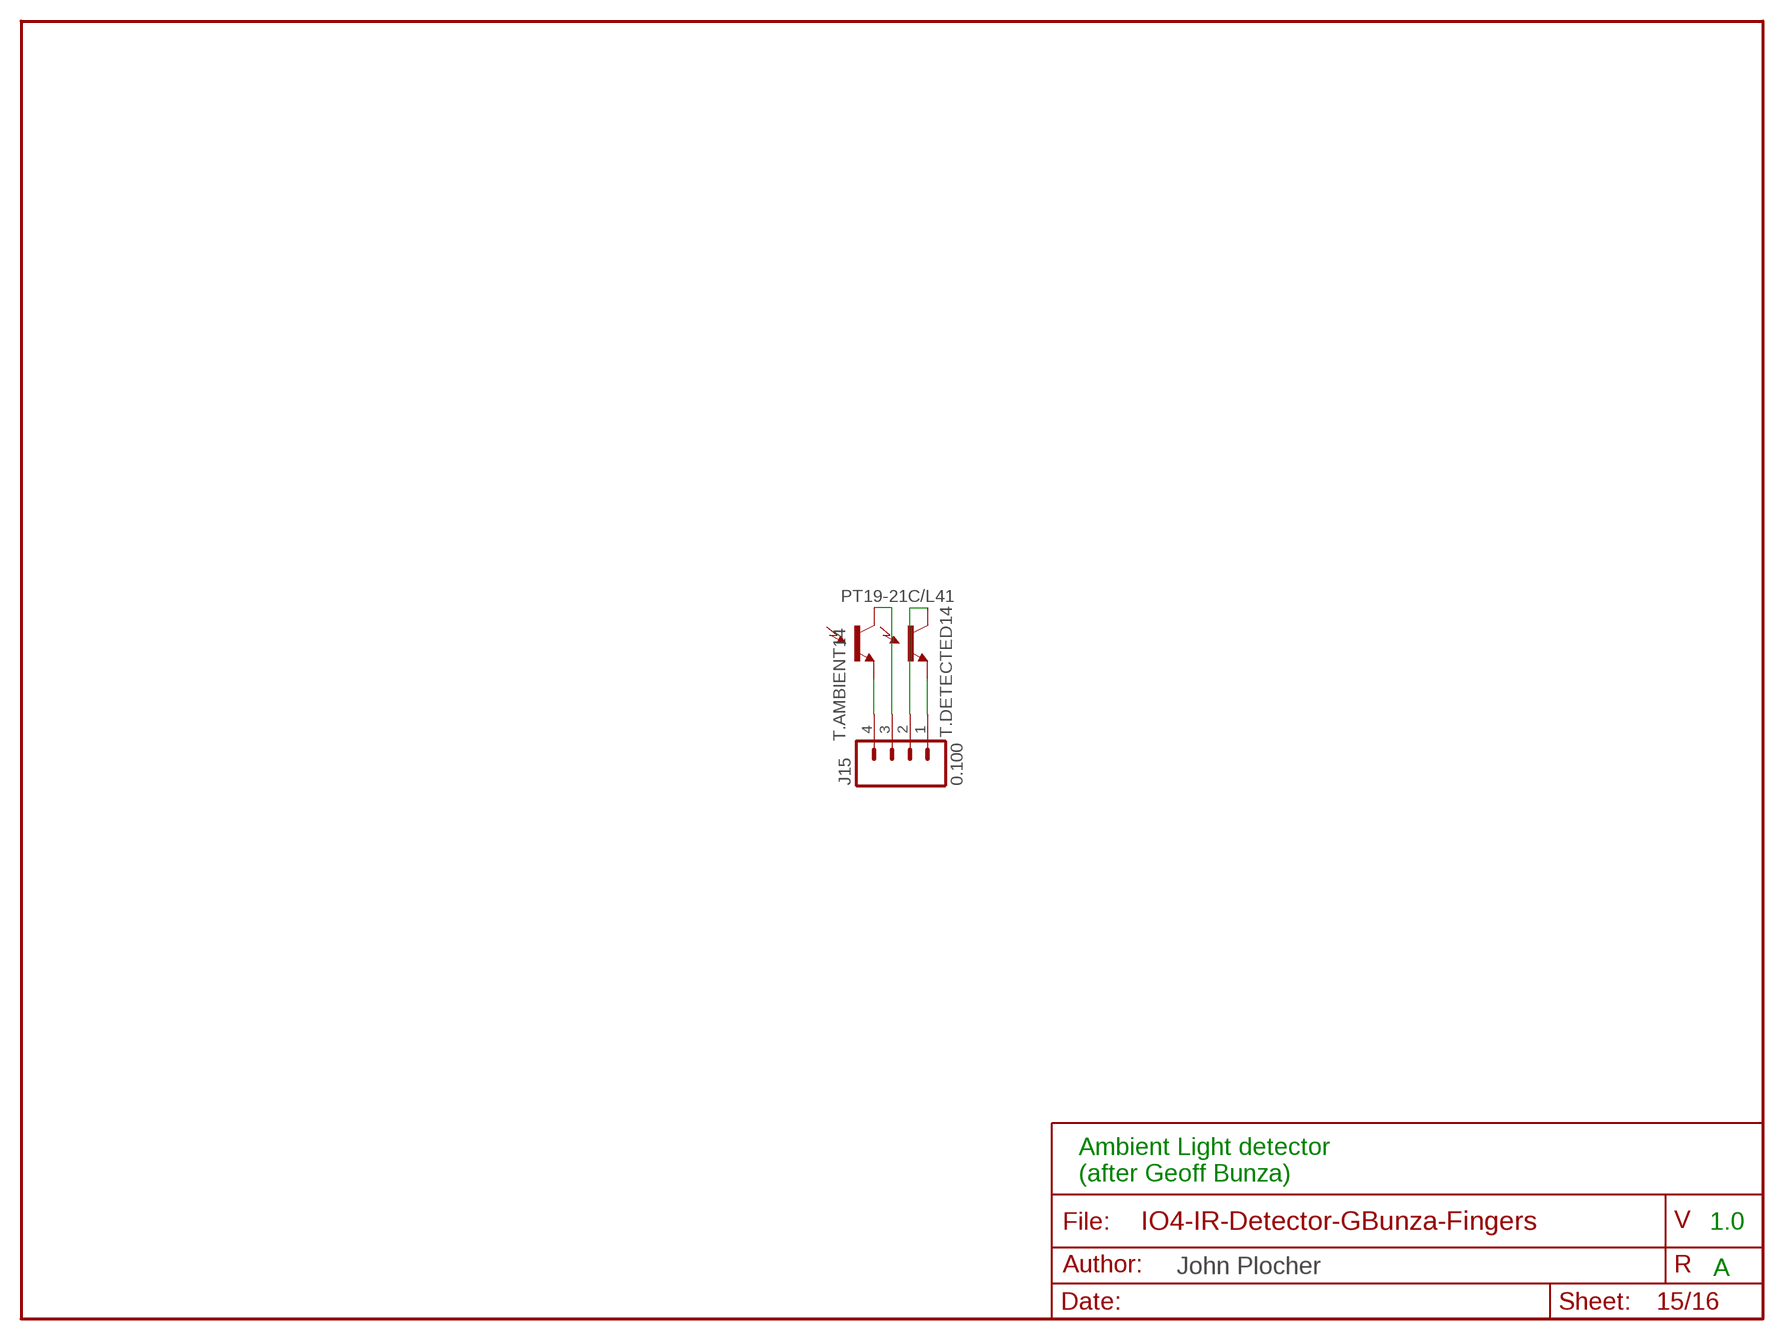
[diagram p14: schematic, sheet 15]
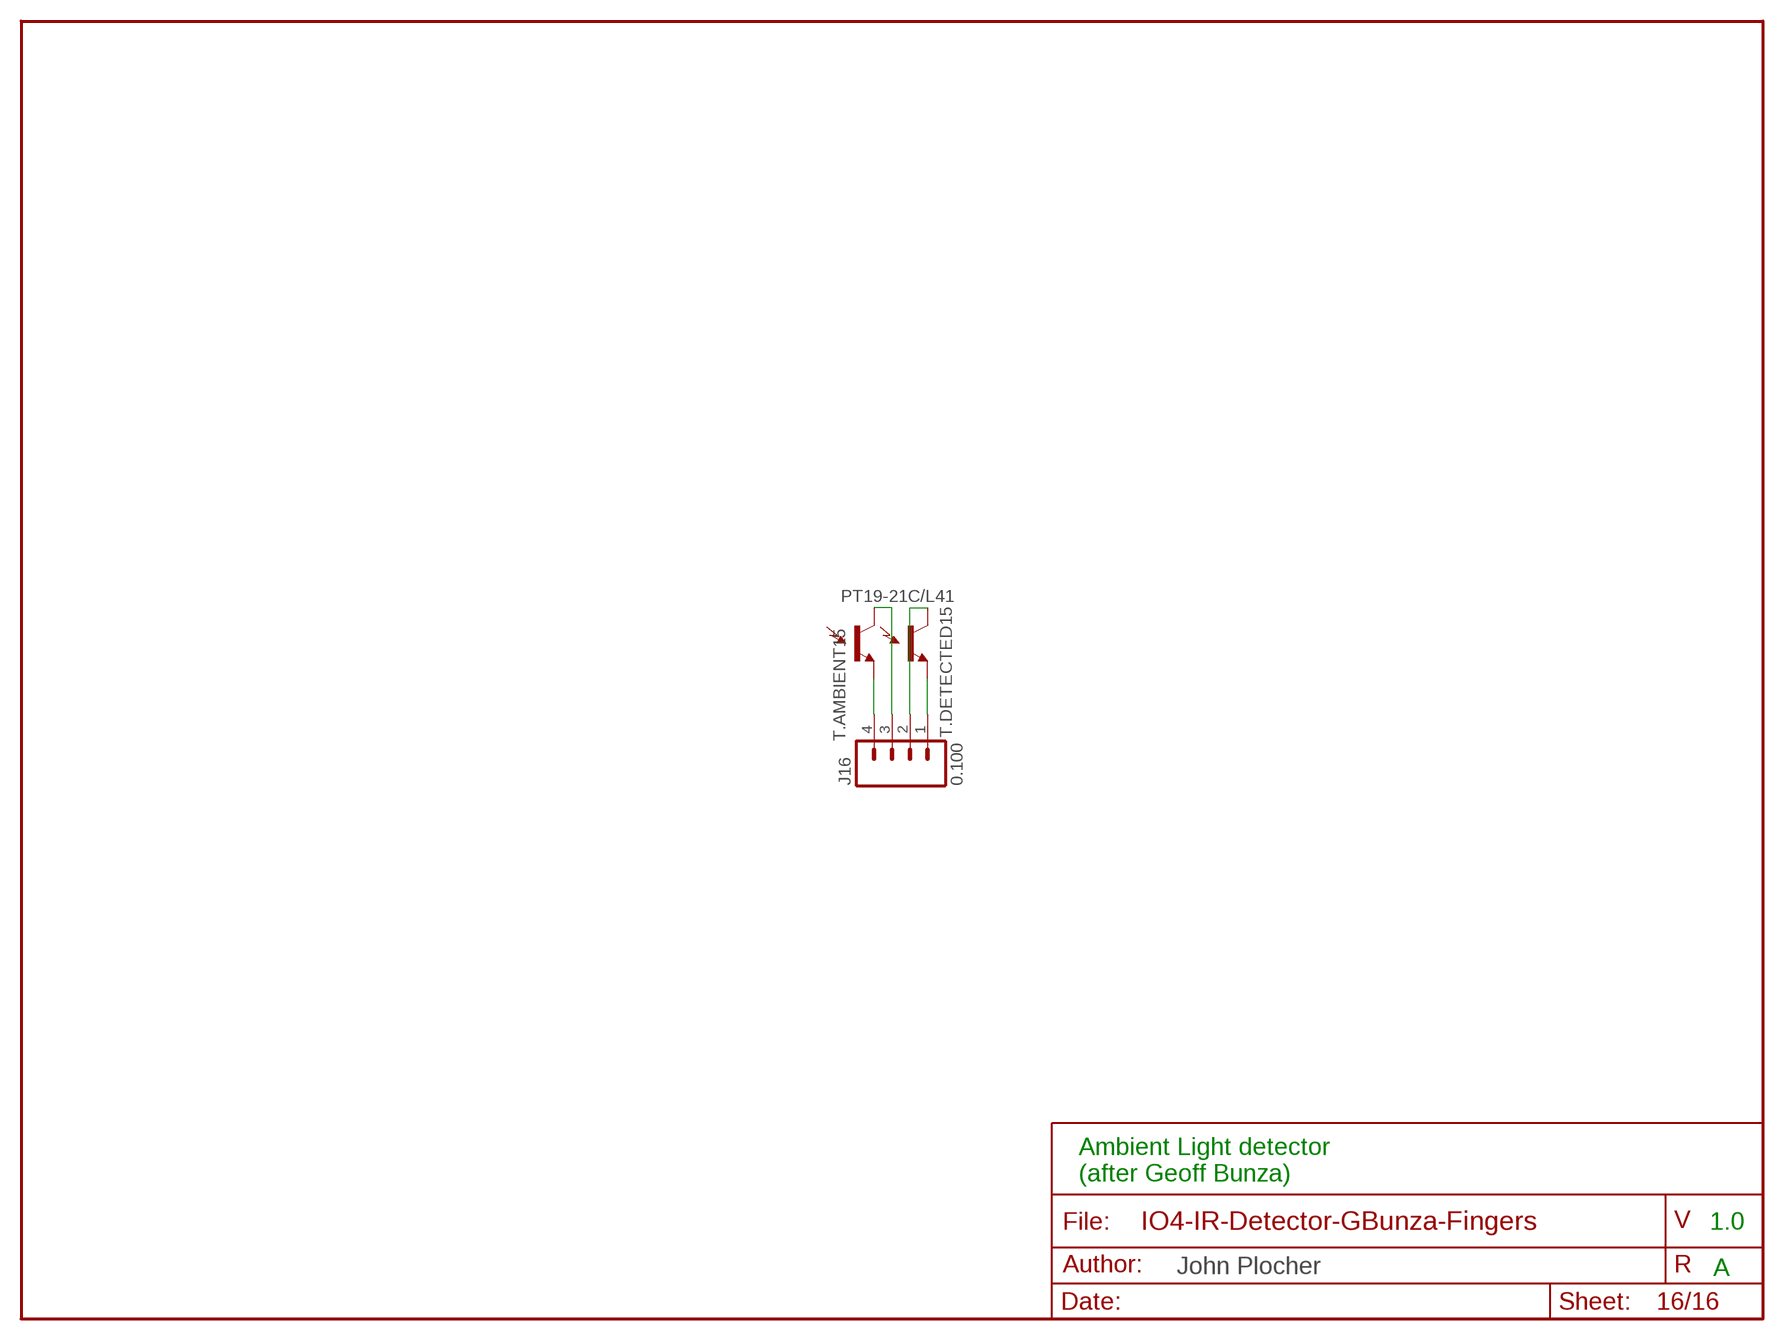
[diagram p15: schematic, sheet 16]

(export (version "E")
  (design (tool "Eeschema 10.0.6"))
  (components
    (comp (ref "J8")
      (value "0.100")
      (footprint "eagle-import:1X04_LOCK")
      (libsource (lib "eagle-import") (part "CONNECTOR-M04LOCK"))
    )
    (comp (ref "T.AMBIENT7")
      (value "PT19-21C/L41")
      (footprint "eagle-import:ALS-PT19")
      (libsource (lib "eagle-import") (part "LIGHTSENSORALS"))
    )
    (comp (ref "T.DETECTED7")
      (value "PT19-21C/L41")
      (footprint "eagle-import:ALS-PT19")
      (libsource (lib "eagle-import") (part "LIGHTSENSORALS"))
    )
    (comp (ref "J11")
      (value "0.100")
      (footprint "eagle-import:1X04_LOCK")
      (libsource (lib "eagle-import") (part "CONNECTOR-M04LOCK"))
    )
    (comp (ref "T.AMBIENT10")
      (value "PT19-21C/L41")
      (footprint "eagle-import:ALS-PT19")
      (libsource (lib "eagle-import") (part "LIGHTSENSORALS"))
    )
    (comp (ref "T.DETECTED10")
      (value "PT19-21C/L41")
      (footprint "eagle-import:ALS-PT19")
      (libsource (lib "eagle-import") (part "LIGHTSENSORALS"))
    )
    (comp (ref "J14")
      (value "0.100")
      (footprint "eagle-import:1X04_LOCK")
      (libsource (lib "eagle-import") (part "CONNECTOR-M04LOCK"))
    )
    (comp (ref "T.AMBIENT13")
      (value "PT19-21C/L41")
      (footprint "eagle-import:ALS-PT19")
      (libsource (lib "eagle-import") (part "LIGHTSENSORALS"))
    )
    (comp (ref "T.DETECTED13")
      (value "PT19-21C/L41")
      (footprint "eagle-import:ALS-PT19")
      (libsource (lib "eagle-import") (part "LIGHTSENSORALS"))
    )
    (comp (ref "J13")
      (value "0.100")
      (footprint "eagle-import:1X04_LOCK")
      (libsource (lib "eagle-import") (part "CONNECTOR-M04LOCK"))
    )
    (comp (ref "T.AMBIENT12")
      (value "PT19-21C/L41")
      (footprint "eagle-import:ALS-PT19")
      (libsource (lib "eagle-import") (part "LIGHTSENSORALS"))
    )
    (comp (ref "T.DETECTED12")
      (value "PT19-21C/L41")
      (footprint "eagle-import:ALS-PT19")
      (libsource (lib "eagle-import") (part "LIGHTSENSORALS"))
    )
    (comp (ref "J15")
      (value "0.100")
      (footprint "eagle-import:1X04_LOCK")
      (libsource (lib "eagle-import") (part "CONNECTOR-M04LOCK"))
    )
    (comp (ref "T.AMBIENT14")
      (value "PT19-21C/L41")
      (footprint "eagle-import:ALS-PT19")
      (libsource (lib "eagle-import") (part "LIGHTSENSORALS"))
    )
    (comp (ref "T.DETECTED14")
      (value "PT19-21C/L41")
      (footprint "eagle-import:ALS-PT19")
      (libsource (lib "eagle-import") (part "LIGHTSENSORALS"))
    )
    (comp (ref "J16")
      (value "0.100")
      (footprint "eagle-import:1X04_LOCK")
      (libsource (lib "eagle-import") (part "CONNECTOR-M04LOCK"))
    )
    (comp (ref "T.AMBIENT15")
      (value "PT19-21C/L41")
      (footprint "eagle-import:ALS-PT19")
      (libsource (lib "eagle-import") (part "LIGHTSENSORALS"))
    )
    (comp (ref "T.DETECTED15")
      (value "PT19-21C/L41")
      (footprint "eagle-import:ALS-PT19")
      (libsource (lib "eagle-import") (part "LIGHTSENSORALS"))
    )
    (comp (ref "J1")
      (value "0.100")
      (footprint "eagle-import:1X04_LOCK")
      (libsource (lib "eagle-import") (part "CONNECTOR-M04LOCK"))
    )
    (comp (ref "T.AMBIENT")
      (value "PT19-21C/L41")
      (footprint "eagle-import:ALS-PT19")
      (libsource (lib "eagle-import") (part "LIGHTSENSORALS"))
    )
    (comp (ref "T.DETECTED")
      (value "PT19-21C/L41")
      (footprint "eagle-import:ALS-PT19")
      (libsource (lib "eagle-import") (part "LIGHTSENSORALS"))
    )
    (comp (ref "J2")
      (value "0.100")
      (footprint "eagle-import:1X04_LOCK")
      (libsource (lib "eagle-import") (part "CONNECTOR-M04LOCK"))
    )
    (comp (ref "T.AMBIENT1")
      (value "PT19-21C/L41")
      (footprint "eagle-import:ALS-PT19")
      (libsource (lib "eagle-import") (part "LIGHTSENSORALS"))
    )
    (comp (ref "T.DETECTED1")
      (value "PT19-21C/L41")
      (footprint "eagle-import:ALS-PT19")
      (libsource (lib "eagle-import") (part "LIGHTSENSORALS"))
    )
    (comp (ref "J5")
      (value "0.100")
      (footprint "eagle-import:1X04_LOCK")
      (libsource (lib "eagle-import") (part "CONNECTOR-M04LOCK"))
    )
    (comp (ref "T.AMBIENT4")
      (value "PT19-21C/L41")
      (footprint "eagle-import:ALS-PT19")
      (libsource (lib "eagle-import") (part "LIGHTSENSORALS"))
    )
    (comp (ref "T.DETECTED4")
      (value "PT19-21C/L41")
      (footprint "eagle-import:ALS-PT19")
      (libsource (lib "eagle-import") (part "LIGHTSENSORALS"))
    )
    (comp (ref "J10")
      (value "0.100")
      (footprint "eagle-import:1X04_LOCK")
      (libsource (lib "eagle-import") (part "CONNECTOR-M04LOCK"))
    )
    (comp (ref "T.AMBIENT9")
      (value "PT19-21C/L41")
      (footprint "eagle-import:ALS-PT19")
      (libsource (lib "eagle-import") (part "LIGHTSENSORALS"))
    )
    (comp (ref "T.DETECTED9")
      (value "PT19-21C/L41")
      (footprint "eagle-import:ALS-PT19")
      (libsource (lib "eagle-import") (part "LIGHTSENSORALS"))
    )
    (comp (ref "J3")
      (value "0.100")
      (footprint "eagle-import:1X04_LOCK")
      (libsource (lib "eagle-import") (part "CONNECTOR-M04LOCK"))
    )
    (comp (ref "T.AMBIENT2")
      (value "PT19-21C/L41")
      (footprint "eagle-import:ALS-PT19")
      (libsource (lib "eagle-import") (part "LIGHTSENSORALS"))
    )
    (comp (ref "T.DETECTED2")
      (value "PT19-21C/L41")
      (footprint "eagle-import:ALS-PT19")
      (libsource (lib "eagle-import") (part "LIGHTSENSORALS"))
    )
    (comp (ref "J4")
      (value "0.100")
      (footprint "eagle-import:1X04_LOCK")
      (libsource (lib "eagle-import") (part "CONNECTOR-M04LOCK"))
    )
    (comp (ref "T.AMBIENT3")
      (value "PT19-21C/L41")
      (footprint "eagle-import:ALS-PT19")
      (libsource (lib "eagle-import") (part "LIGHTSENSORALS"))
    )
    (comp (ref "T.DETECTED3")
      (value "PT19-21C/L41")
      (footprint "eagle-import:ALS-PT19")
      (libsource (lib "eagle-import") (part "LIGHTSENSORALS"))
    )
    (comp (ref "J9")
      (value "0.100")
      (footprint "eagle-import:1X04_LOCK")
      (libsource (lib "eagle-import") (part "CONNECTOR-M04LOCK"))
    )
    (comp (ref "T.AMBIENT8")
      (value "PT19-21C/L41")
      (footprint "eagle-import:ALS-PT19")
      (libsource (lib "eagle-import") (part "LIGHTSENSORALS"))
    )
    (comp (ref "T.DETECTED8")
      (value "PT19-21C/L41")
      (footprint "eagle-import:ALS-PT19")
      (libsource (lib "eagle-import") (part "LIGHTSENSORALS"))
    )
    (comp (ref "J12")
      (value "0.100")
      (footprint "eagle-import:1X04_LOCK")
      (libsource (lib "eagle-import") (part "CONNECTOR-M04LOCK"))
    )
    (comp (ref "T.AMBIENT11")
      (value "PT19-21C/L41")
      (footprint "eagle-import:ALS-PT19")
      (libsource (lib "eagle-import") (part "LIGHTSENSORALS"))
    )
    (comp (ref "T.DETECTED11")
      (value "PT19-21C/L41")
      (footprint "eagle-import:ALS-PT19")
      (libsource (lib "eagle-import") (part "LIGHTSENSORALS"))
    )
    (comp (ref "J7")
      (value "0.100")
      (footprint "eagle-import:1X04_LOCK")
      (libsource (lib "eagle-import") (part "CONNECTOR-M04LOCK"))
    )
    (comp (ref "T.AMBIENT6")
      (value "PT19-21C/L41")
      (footprint "eagle-import:ALS-PT19")
      (libsource (lib "eagle-import") (part "LIGHTSENSORALS"))
    )
    (comp (ref "T.DETECTED6")
      (value "PT19-21C/L41")
      (footprint "eagle-import:ALS-PT19")
      (libsource (lib "eagle-import") (part "LIGHTSENSORALS"))
    )
    (comp (ref "J6")
      (value "0.100")
      (footprint "eagle-import:1X04_LOCK")
      (libsource (lib "eagle-import") (part "CONNECTOR-M04LOCK"))
    )
    (comp (ref "T.AMBIENT5")
      (value "PT19-21C/L41")
      (footprint "eagle-import:ALS-PT19")
      (libsource (lib "eagle-import") (part "LIGHTSENSORALS"))
    )
    (comp (ref "T.DETECTED5")
      (value "PT19-21C/L41")
      (footprint "eagle-import:ALS-PT19")
      (libsource (lib "eagle-import") (part "LIGHTSENSORALS"))
    )
  )
  (nets
    (net (code "1") (name "Net-(T.AMBIENT-C1)") (class "Default")
      (node (ref "J1") (pin "3") (pinfunction "3_3") (pintype "passive"))
      (node (ref "T.AMBIENT") (pin "C") (pinfunction "C1_C") (pintype "passive"))
    )
    (net (code "2") (name "Net-(T.AMBIENT-E1)") (class "Default")
      (node (ref "J1") (pin "4") (pinfunction "4_4") (pintype "passive"))
      (node (ref "T.AMBIENT") (pin "E") (pinfunction "E1_E") (pintype "passive"))
    )
    (net (code "3") (name "Net-(T.AMBIENT1-C1)") (class "Default")
      (node (ref "J2") (pin "3") (pinfunction "3_3") (pintype "passive"))
      (node (ref "T.AMBIENT1") (pin "C") (pinfunction "C1_C") (pintype "passive"))
    )
    (net (code "4") (name "Net-(T.AMBIENT1-E1)") (class "Default")
      (node (ref "J2") (pin "4") (pinfunction "4_4") (pintype "passive"))
      (node (ref "T.AMBIENT1") (pin "E") (pinfunction "E1_E") (pintype "passive"))
    )
    (net (code "5") (name "Net-(T.AMBIENT2-C1)") (class "Default")
      (node (ref "J3") (pin "3") (pinfunction "3_3") (pintype "passive"))
      (node (ref "T.AMBIENT2") (pin "C") (pinfunction "C1_C") (pintype "passive"))
    )
    (net (code "6") (name "Net-(T.AMBIENT2-E1)") (class "Default")
      (node (ref "J3") (pin "4") (pinfunction "4_4") (pintype "passive"))
      (node (ref "T.AMBIENT2") (pin "E") (pinfunction "E1_E") (pintype "passive"))
    )
    (net (code "7") (name "Net-(T.AMBIENT3-C1)") (class "Default")
      (node (ref "J4") (pin "3") (pinfunction "3_3") (pintype "passive"))
      (node (ref "T.AMBIENT3") (pin "C") (pinfunction "C1_C") (pintype "passive"))
    )
    (net (code "8") (name "Net-(T.AMBIENT3-E1)") (class "Default")
      (node (ref "J4") (pin "4") (pinfunction "4_4") (pintype "passive"))
      (node (ref "T.AMBIENT3") (pin "E") (pinfunction "E1_E") (pintype "passive"))
    )
    (net (code "9") (name "Net-(T.AMBIENT4-C1)") (class "Default")
      (node (ref "J5") (pin "3") (pinfunction "3_3") (pintype "passive"))
      (node (ref "T.AMBIENT4") (pin "C") (pinfunction "C1_C") (pintype "passive"))
    )
    (net (code "10") (name "Net-(T.AMBIENT4-E1)") (class "Default")
      (node (ref "J5") (pin "4") (pinfunction "4_4") (pintype "passive"))
      (node (ref "T.AMBIENT4") (pin "E") (pinfunction "E1_E") (pintype "passive"))
    )
    (net (code "11") (name "Net-(T.AMBIENT5-C1)") (class "Default")
      (node (ref "J6") (pin "3") (pinfunction "3_3") (pintype "passive"))
      (node (ref "T.AMBIENT5") (pin "C") (pinfunction "C1_C") (pintype "passive"))
    )
    (net (code "12") (name "Net-(T.AMBIENT5-E1)") (class "Default")
      (node (ref "J6") (pin "4") (pinfunction "4_4") (pintype "passive"))
      (node (ref "T.AMBIENT5") (pin "E") (pinfunction "E1_E") (pintype "passive"))
    )
    (net (code "13") (name "Net-(T.AMBIENT6-C1)") (class "Default")
      (node (ref "J7") (pin "3") (pinfunction "3_3") (pintype "passive"))
      (node (ref "T.AMBIENT6") (pin "C") (pinfunction "C1_C") (pintype "passive"))
    )
    (net (code "14") (name "Net-(T.AMBIENT6-E1)") (class "Default")
      (node (ref "J7") (pin "4") (pinfunction "4_4") (pintype "passive"))
      (node (ref "T.AMBIENT6") (pin "E") (pinfunction "E1_E") (pintype "passive"))
    )
    (net (code "15") (name "Net-(T.AMBIENT7-C1)") (class "Default")
      (node (ref "J8") (pin "3") (pinfunction "3_3") (pintype "passive"))
      (node (ref "T.AMBIENT7") (pin "C") (pinfunction "C1_C") (pintype "passive"))
    )
    (net (code "16") (name "Net-(T.AMBIENT7-E1)") (class "Default")
      (node (ref "J8") (pin "4") (pinfunction "4_4") (pintype "passive"))
      (node (ref "T.AMBIENT7") (pin "E") (pinfunction "E1_E") (pintype "passive"))
    )
    (net (code "17") (name "Net-(T.AMBIENT8-C1)") (class "Default")
      (node (ref "J9") (pin "3") (pinfunction "3_3") (pintype "passive"))
      (node (ref "T.AMBIENT8") (pin "C") (pinfunction "C1_C") (pintype "passive"))
    )
    (net (code "18") (name "Net-(T.AMBIENT8-E1)") (class "Default")
      (node (ref "J9") (pin "4") (pinfunction "4_4") (pintype "passive"))
      (node (ref "T.AMBIENT8") (pin "E") (pinfunction "E1_E") (pintype "passive"))
    )
    (net (code "19") (name "Net-(T.AMBIENT9-C1)") (class "Default")
      (node (ref "J10") (pin "3") (pinfunction "3_3") (pintype "passive"))
      (node (ref "T.AMBIENT9") (pin "C") (pinfunction "C1_C") (pintype "passive"))
    )
    (net (code "20") (name "Net-(T.AMBIENT9-E1)") (class "Default")
      (node (ref "J10") (pin "4") (pinfunction "4_4") (pintype "passive"))
      (node (ref "T.AMBIENT9") (pin "E") (pinfunction "E1_E") (pintype "passive"))
    )
    (net (code "21") (name "Net-(T.AMBIENT10-C1)") (class "Default")
      (node (ref "J11") (pin "3") (pinfunction "3_3") (pintype "passive"))
      (node (ref "T.AMBIENT10") (pin "C") (pinfunction "C1_C") (pintype "passive"))
    )
    (net (code "22") (name "Net-(T.AMBIENT10-E1)") (class "Default")
      (node (ref "J11") (pin "4") (pinfunction "4_4") (pintype "passive"))
      (node (ref "T.AMBIENT10") (pin "E") (pinfunction "E1_E") (pintype "passive"))
    )
    (net (code "23") (name "Net-(T.AMBIENT11-C1)") (class "Default")
      (node (ref "J12") (pin "3") (pinfunction "3_3") (pintype "passive"))
      (node (ref "T.AMBIENT11") (pin "C") (pinfunction "C1_C") (pintype "passive"))
    )
    (net (code "24") (name "Net-(T.AMBIENT11-E1)") (class "Default")
      (node (ref "J12") (pin "4") (pinfunction "4_4") (pintype "passive"))
      (node (ref "T.AMBIENT11") (pin "E") (pinfunction "E1_E") (pintype "passive"))
    )
    (net (code "25") (name "Net-(T.AMBIENT12-C1)") (class "Default")
      (node (ref "J13") (pin "3") (pinfunction "3_3") (pintype "passive"))
      (node (ref "T.AMBIENT12") (pin "C") (pinfunction "C1_C") (pintype "passive"))
    )
    (net (code "26") (name "Net-(T.AMBIENT12-E1)") (class "Default")
      (node (ref "J13") (pin "4") (pinfunction "4_4") (pintype "passive"))
      (node (ref "T.AMBIENT12") (pin "E") (pinfunction "E1_E") (pintype "passive"))
    )
    (net (code "27") (name "Net-(T.AMBIENT13-C1)") (class "Default")
      (node (ref "J14") (pin "3") (pinfunction "3_3") (pintype "passive"))
      (node (ref "T.AMBIENT13") (pin "C") (pinfunction "C1_C") (pintype "passive"))
    )
    (net (code "28") (name "Net-(T.AMBIENT13-E1)") (class "Default")
      (node (ref "J14") (pin "4") (pinfunction "4_4") (pintype "passive"))
      (node (ref "T.AMBIENT13") (pin "E") (pinfunction "E1_E") (pintype "passive"))
    )
    (net (code "29") (name "Net-(T.AMBIENT14-C1)") (class "Default")
      (node (ref "J15") (pin "3") (pinfunction "3_3") (pintype "passive"))
      (node (ref "T.AMBIENT14") (pin "C") (pinfunction "C1_C") (pintype "passive"))
    )
    (net (code "30") (name "Net-(T.AMBIENT14-E1)") (class "Default")
      (node (ref "J15") (pin "4") (pinfunction "4_4") (pintype "passive"))
      (node (ref "T.AMBIENT14") (pin "E") (pinfunction "E1_E") (pintype "passive"))
    )
    (net (code "31") (name "Net-(T.AMBIENT15-C1)") (class "Default")
      (node (ref "J16") (pin "3") (pinfunction "3_3") (pintype "passive"))
      (node (ref "T.AMBIENT15") (pin "C") (pinfunction "C1_C") (pintype "passive"))
    )
    (net (code "32") (name "Net-(T.AMBIENT15-E1)") (class "Default")
      (node (ref "J16") (pin "4") (pinfunction "4_4") (pintype "passive"))
      (node (ref "T.AMBIENT15") (pin "E") (pinfunction "E1_E") (pintype "passive"))
    )
    (net (code "33") (name "Net-(T.DETECTED-C1)") (class "Default")
      (node (ref "J1") (pin "2") (pinfunction "2_2") (pintype "passive"))
      (node (ref "T.DETECTED") (pin "C") (pinfunction "C1_C") (pintype "passive"))
    )
    (net (code "34") (name "Net-(T.DETECTED-E1)") (class "Default")
      (node (ref "J1") (pin "1") (pinfunction "1_1") (pintype "passive"))
      (node (ref "T.DETECTED") (pin "E") (pinfunction "E1_E") (pintype "passive"))
    )
    (net (code "35") (name "Net-(T.DETECTED1-C1)") (class "Default")
      (node (ref "J2") (pin "2") (pinfunction "2_2") (pintype "passive"))
      (node (ref "T.DETECTED1") (pin "C") (pinfunction "C1_C") (pintype "passive"))
    )
    (net (code "36") (name "Net-(T.DETECTED1-E1)") (class "Default")
      (node (ref "J2") (pin "1") (pinfunction "1_1") (pintype "passive"))
      (node (ref "T.DETECTED1") (pin "E") (pinfunction "E1_E") (pintype "passive"))
    )
    (net (code "37") (name "Net-(T.DETECTED2-C1)") (class "Default")
      (node (ref "J3") (pin "2") (pinfunction "2_2") (pintype "passive"))
      (node (ref "T.DETECTED2") (pin "C") (pinfunction "C1_C") (pintype "passive"))
    )
    (net (code "38") (name "Net-(T.DETECTED2-E1)") (class "Default")
      (node (ref "J3") (pin "1") (pinfunction "1_1") (pintype "passive"))
      (node (ref "T.DETECTED2") (pin "E") (pinfunction "E1_E") (pintype "passive"))
    )
    (net (code "39") (name "Net-(T.DETECTED3-C1)") (class "Default")
      (node (ref "J4") (pin "2") (pinfunction "2_2") (pintype "passive"))
      (node (ref "T.DETECTED3") (pin "C") (pinfunction "C1_C") (pintype "passive"))
    )
    (net (code "40") (name "Net-(T.DETECTED3-E1)") (class "Default")
      (node (ref "J4") (pin "1") (pinfunction "1_1") (pintype "passive"))
      (node (ref "T.DETECTED3") (pin "E") (pinfunction "E1_E") (pintype "passive"))
    )
    (net (code "41") (name "Net-(T.DETECTED4-C1)") (class "Default")
      (node (ref "J5") (pin "2") (pinfunction "2_2") (pintype "passive"))
      (node (ref "T.DETECTED4") (pin "C") (pinfunction "C1_C") (pintype "passive"))
    )
    (net (code "42") (name "Net-(T.DETECTED4-E1)") (class "Default")
      (node (ref "J5") (pin "1") (pinfunction "1_1") (pintype "passive"))
      (node (ref "T.DETECTED4") (pin "E") (pinfunction "E1_E") (pintype "passive"))
    )
    (net (code "43") (name "Net-(T.DETECTED5-C1)") (class "Default")
      (node (ref "J6") (pin "2") (pinfunction "2_2") (pintype "passive"))
      (node (ref "T.DETECTED5") (pin "C") (pinfunction "C1_C") (pintype "passive"))
    )
    (net (code "44") (name "Net-(T.DETECTED5-E1)") (class "Default")
      (node (ref "J6") (pin "1") (pinfunction "1_1") (pintype "passive"))
      (node (ref "T.DETECTED5") (pin "E") (pinfunction "E1_E") (pintype "passive"))
    )
    (net (code "45") (name "Net-(T.DETECTED6-C1)") (class "Default")
      (node (ref "J7") (pin "2") (pinfunction "2_2") (pintype "passive"))
      (node (ref "T.DETECTED6") (pin "C") (pinfunction "C1_C") (pintype "passive"))
    )
    (net (code "46") (name "Net-(T.DETECTED6-E1)") (class "Default")
      (node (ref "J7") (pin "1") (pinfunction "1_1") (pintype "passive"))
      (node (ref "T.DETECTED6") (pin "E") (pinfunction "E1_E") (pintype "passive"))
    )
    (net (code "47") (name "Net-(T.DETECTED7-C1)") (class "Default")
      (node (ref "J8") (pin "2") (pinfunction "2_2") (pintype "passive"))
      (node (ref "T.DETECTED7") (pin "C") (pinfunction "C1_C") (pintype "passive"))
    )
    (net (code "48") (name "Net-(T.DETECTED7-E1)") (class "Default")
      (node (ref "J8") (pin "1") (pinfunction "1_1") (pintype "passive"))
      (node (ref "T.DETECTED7") (pin "E") (pinfunction "E1_E") (pintype "passive"))
    )
    (net (code "49") (name "Net-(T.DETECTED8-C1)") (class "Default")
      (node (ref "J9") (pin "2") (pinfunction "2_2") (pintype "passive"))
      (node (ref "T.DETECTED8") (pin "C") (pinfunction "C1_C") (pintype "passive"))
    )
    (net (code "50") (name "Net-(T.DETECTED8-E1)") (class "Default")
      (node (ref "J9") (pin "1") (pinfunction "1_1") (pintype "passive"))
      (node (ref "T.DETECTED8") (pin "E") (pinfunction "E1_E") (pintype "passive"))
    )
    (net (code "51") (name "Net-(T.DETECTED9-C1)") (class "Default")
      (node (ref "J10") (pin "2") (pinfunction "2_2") (pintype "passive"))
      (node (ref "T.DETECTED9") (pin "C") (pinfunction "C1_C") (pintype "passive"))
    )
    (net (code "52") (name "Net-(T.DETECTED9-E1)") (class "Default")
      (node (ref "J10") (pin "1") (pinfunction "1_1") (pintype "passive"))
      (node (ref "T.DETECTED9") (pin "E") (pinfunction "E1_E") (pintype "passive"))
    )
    (net (code "53") (name "Net-(T.DETECTED10-C1)") (class "Default")
      (node (ref "J11") (pin "2") (pinfunction "2_2") (pintype "passive"))
      (node (ref "T.DETECTED10") (pin "C") (pinfunction "C1_C") (pintype "passive"))
    )
    (net (code "54") (name "Net-(T.DETECTED10-E1)") (class "Default")
      (node (ref "J11") (pin "1") (pinfunction "1_1") (pintype "passive"))
      (node (ref "T.DETECTED10") (pin "E") (pinfunction "E1_E") (pintype "passive"))
    )
    (net (code "55") (name "Net-(T.DETECTED11-C1)") (class "Default")
      (node (ref "J12") (pin "2") (pinfunction "2_2") (pintype "passive"))
      (node (ref "T.DETECTED11") (pin "C") (pinfunction "C1_C") (pintype "passive"))
    )
    (net (code "56") (name "Net-(T.DETECTED11-E1)") (class "Default")
      (node (ref "J12") (pin "1") (pinfunction "1_1") (pintype "passive"))
      (node (ref "T.DETECTED11") (pin "E") (pinfunction "E1_E") (pintype "passive"))
    )
    (net (code "57") (name "Net-(T.DETECTED12-C1)") (class "Default")
      (node (ref "J13") (pin "2") (pinfunction "2_2") (pintype "passive"))
      (node (ref "T.DETECTED12") (pin "C") (pinfunction "C1_C") (pintype "passive"))
    )
    (net (code "58") (name "Net-(T.DETECTED12-E1)") (class "Default")
      (node (ref "J13") (pin "1") (pinfunction "1_1") (pintype "passive"))
      (node (ref "T.DETECTED12") (pin "E") (pinfunction "E1_E") (pintype "passive"))
    )
    (net (code "59") (name "Net-(T.DETECTED13-C1)") (class "Default")
      (node (ref "J14") (pin "2") (pinfunction "2_2") (pintype "passive"))
      (node (ref "T.DETECTED13") (pin "C") (pinfunction "C1_C") (pintype "passive"))
    )
    (net (code "60") (name "Net-(T.DETECTED13-E1)") (class "Default")
      (node (ref "J14") (pin "1") (pinfunction "1_1") (pintype "passive"))
      (node (ref "T.DETECTED13") (pin "E") (pinfunction "E1_E") (pintype "passive"))
    )
    (net (code "61") (name "Net-(T.DETECTED14-C1)") (class "Default")
      (node (ref "J15") (pin "2") (pinfunction "2_2") (pintype "passive"))
      (node (ref "T.DETECTED14") (pin "C") (pinfunction "C1_C") (pintype "passive"))
    )
    (net (code "62") (name "Net-(T.DETECTED14-E1)") (class "Default")
      (node (ref "J15") (pin "1") (pinfunction "1_1") (pintype "passive"))
      (node (ref "T.DETECTED14") (pin "E") (pinfunction "E1_E") (pintype "passive"))
    )
    (net (code "63") (name "Net-(T.DETECTED15-C1)") (class "Default")
      (node (ref "J16") (pin "2") (pinfunction "2_2") (pintype "passive"))
      (node (ref "T.DETECTED15") (pin "C") (pinfunction "C1_C") (pintype "passive"))
    )
    (net (code "64") (name "Net-(T.DETECTED15-E1)") (class "Default")
      (node (ref "J16") (pin "1") (pinfunction "1_1") (pintype "passive"))
      (node (ref "T.DETECTED15") (pin "E") (pinfunction "E1_E") (pintype "passive"))
    )
  )
)
